# LED1_2.net
KiCad netlist of a schematic drawn in Altium Designer
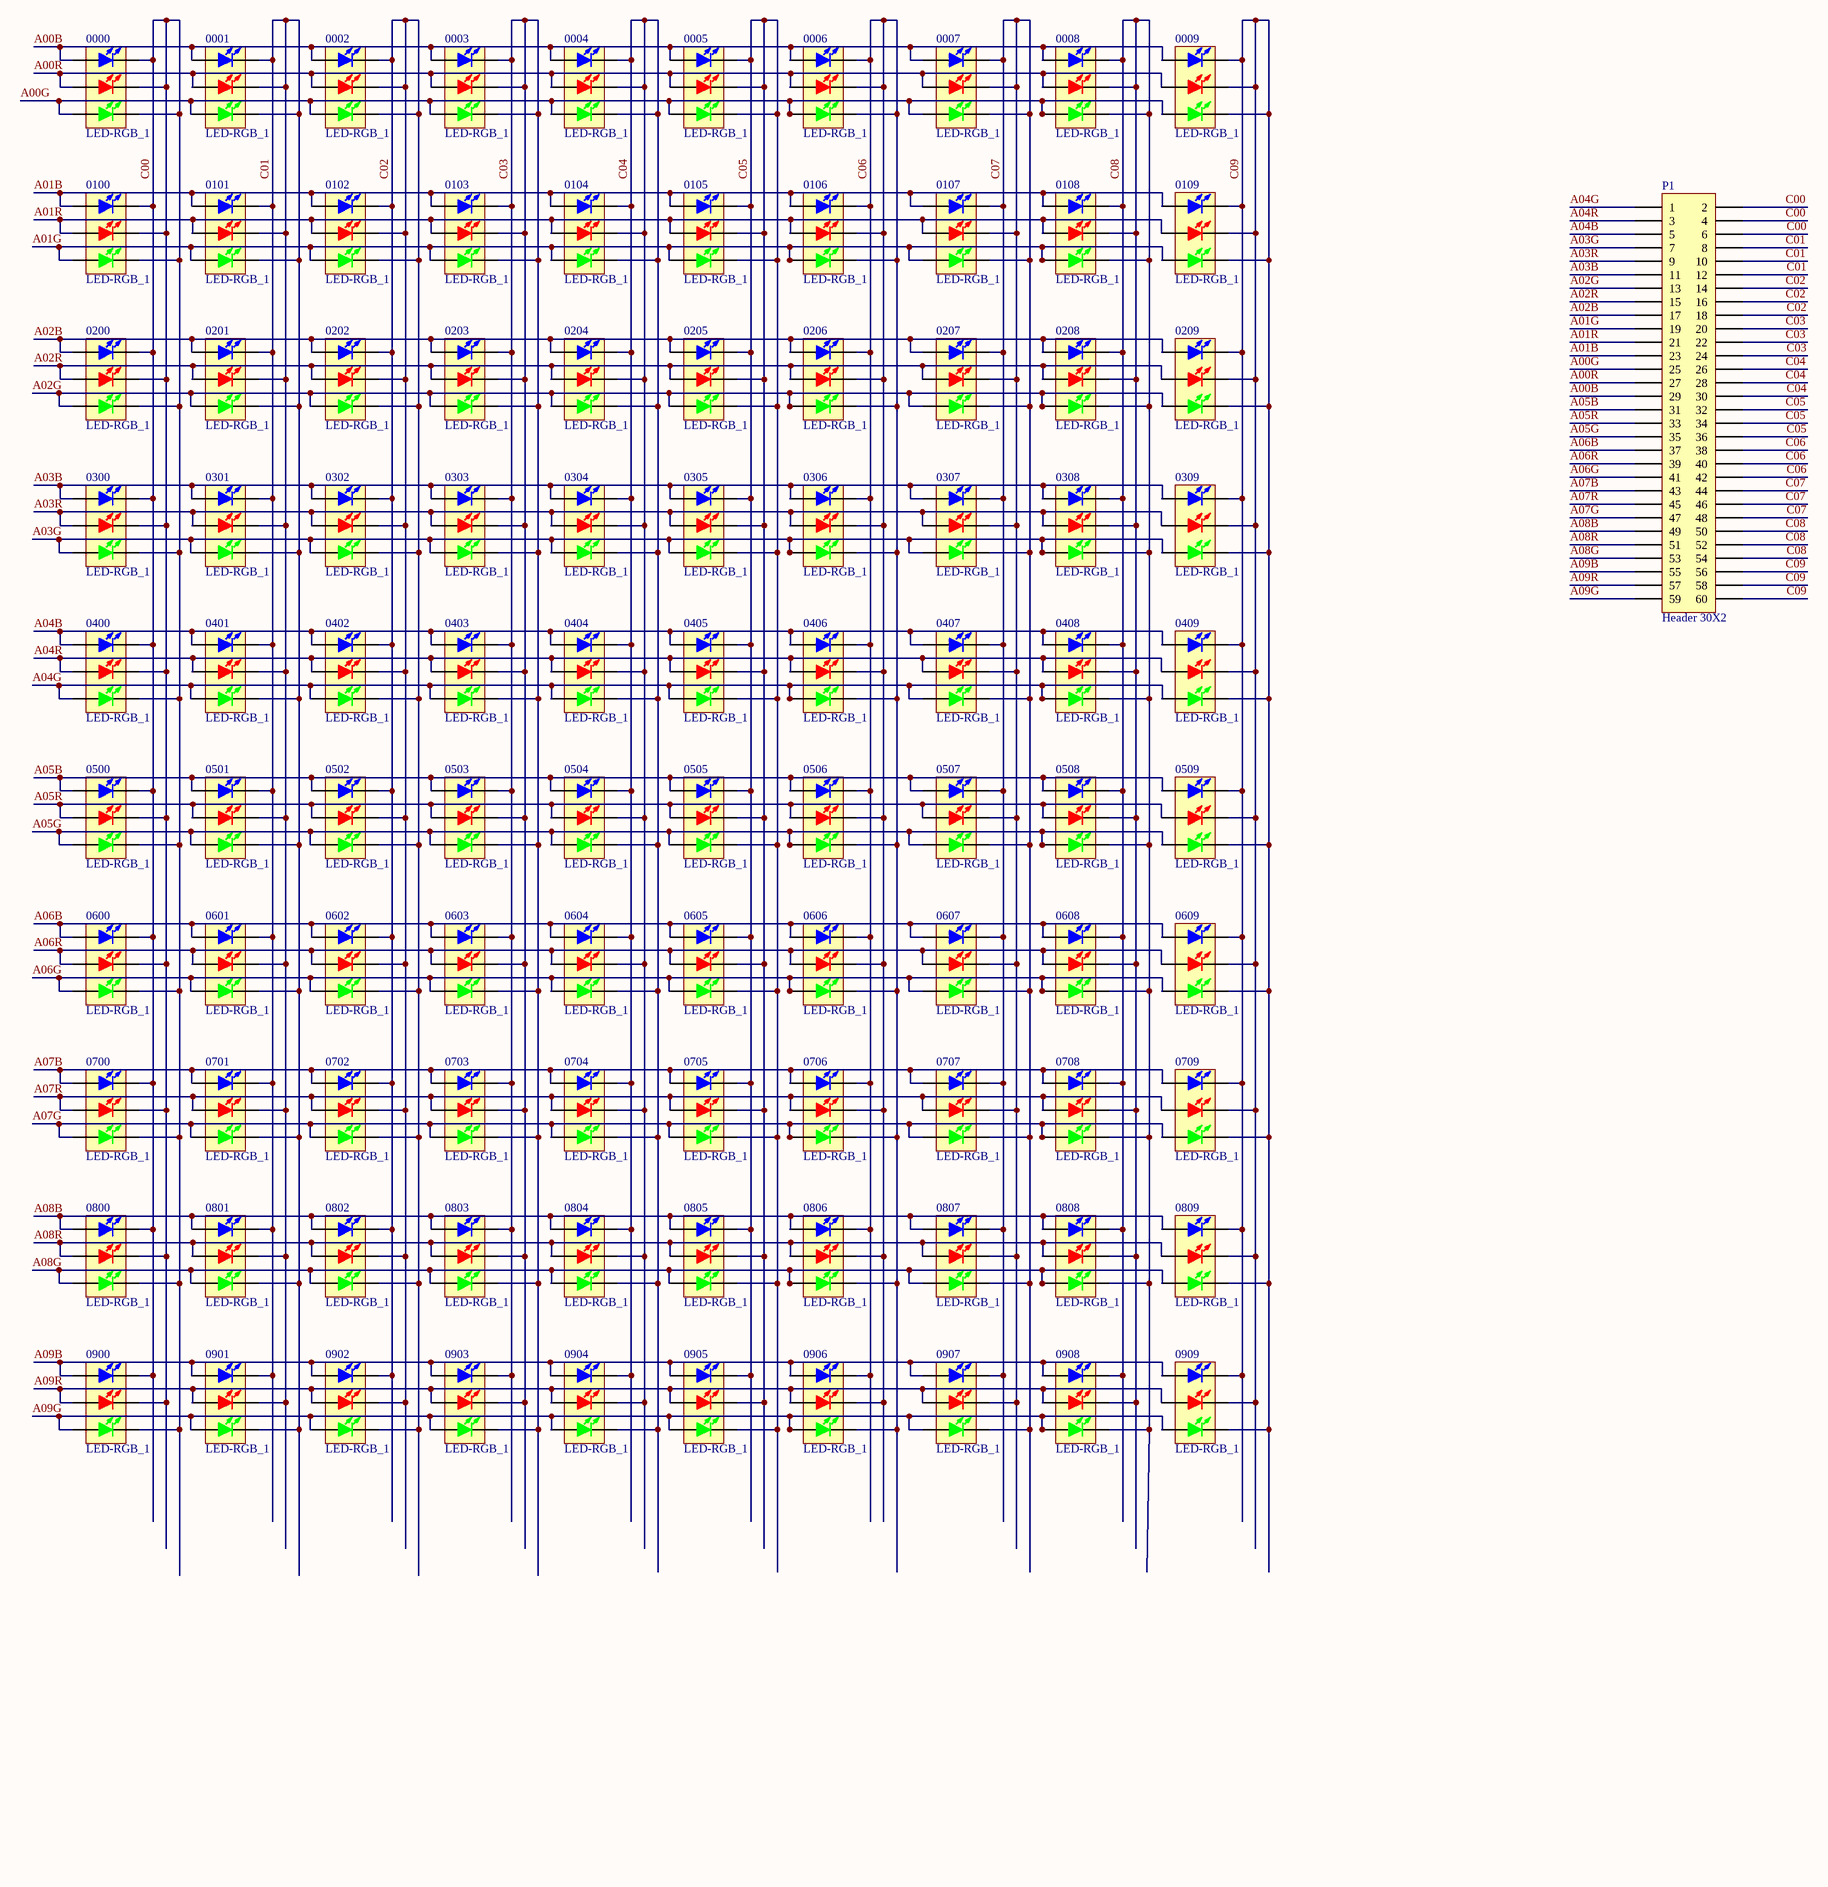
[diagram p0: LED1_2.SchDoc]

(export (version "E")
  (design (tool "Eeschema 10.0.6"))
  (components
    (comp (ref "0000")
      (value "LED-RGB_1")
      (footprint "LED 5050")
      (description "三基色LED,正负脚相对")
      (fields (field (name "版权归属") "源创客"))
      (libsource (lib "IL") (part "LED-RGB_1"))
    )
    (comp (ref "0001")
      (value "LED-RGB_1")
      (footprint "LED 5050")
      (description "三基色LED,正负脚相对")
      (fields (field (name "版权归属") "源创客"))
      (libsource (lib "IL") (part "LED-RGB_1"))
    )
    (comp (ref "0002")
      (value "LED-RGB_1")
      (footprint "LED 5050")
      (description "三基色LED,正负脚相对")
      (fields (field (name "版权归属") "源创客"))
      (libsource (lib "IL") (part "LED-RGB_1"))
    )
    (comp (ref "0003")
      (value "LED-RGB_1")
      (footprint "LED 5050")
      (description "三基色LED,正负脚相对")
      (fields (field (name "版权归属") "源创客"))
      (libsource (lib "IL") (part "LED-RGB_1"))
    )
    (comp (ref "0004")
      (value "LED-RGB_1")
      (footprint "LED 5050")
      (description "三基色LED,正负脚相对")
      (fields (field (name "版权归属") "源创客"))
      (libsource (lib "IL") (part "LED-RGB_1"))
    )
    (comp (ref "0005")
      (value "LED-RGB_1")
      (footprint "LED 5050")
      (description "三基色LED,正负脚相对")
      (fields (field (name "版权归属") "源创客"))
      (libsource (lib "IL") (part "LED-RGB_1"))
    )
    (comp (ref "0006")
      (value "LED-RGB_1")
      (footprint "LED 5050")
      (description "三基色LED,正负脚相对")
      (fields (field (name "版权归属") "源创客"))
      (libsource (lib "IL") (part "LED-RGB_1"))
    )
    (comp (ref "0007")
      (value "LED-RGB_1")
      (footprint "LED 5050")
      (description "三基色LED,正负脚相对")
      (fields (field (name "版权归属") "源创客"))
      (libsource (lib "IL") (part "LED-RGB_1"))
    )
    (comp (ref "0008")
      (value "LED-RGB_1")
      (footprint "LED 5050")
      (description "三基色LED,正负脚相对")
      (fields (field (name "版权归属") "源创客"))
      (libsource (lib "IL") (part "LED-RGB_1"))
    )
    (comp (ref "0009")
      (value "LED-RGB_1")
      (footprint "LED 5050")
      (description "三基色LED,正负脚相对")
      (fields (field (name "版权归属") "源创客"))
      (libsource (lib "IL") (part "LED-RGB_1"))
    )
    (comp (ref "0100")
      (value "LED-RGB_1")
      (footprint "LED 5050")
      (description "三基色LED,正负脚相对")
      (fields (field (name "版权归属") "源创客"))
      (libsource (lib "IL") (part "LED-RGB_1"))
    )
    (comp (ref "0101")
      (value "LED-RGB_1")
      (footprint "LED 5050")
      (description "三基色LED,正负脚相对")
      (fields (field (name "版权归属") "源创客"))
      (libsource (lib "IL") (part "LED-RGB_1"))
    )
    (comp (ref "0102")
      (value "LED-RGB_1")
      (footprint "LED 5050")
      (description "三基色LED,正负脚相对")
      (fields (field (name "版权归属") "源创客"))
      (libsource (lib "IL") (part "LED-RGB_1"))
    )
    (comp (ref "0103")
      (value "LED-RGB_1")
      (footprint "LED 5050")
      (description "三基色LED,正负脚相对")
      (fields (field (name "版权归属") "源创客"))
      (libsource (lib "IL") (part "LED-RGB_1"))
    )
    (comp (ref "0104")
      (value "LED-RGB_1")
      (footprint "LED 5050")
      (description "三基色LED,正负脚相对")
      (fields (field (name "版权归属") "源创客"))
      (libsource (lib "IL") (part "LED-RGB_1"))
    )
    (comp (ref "0105")
      (value "LED-RGB_1")
      (footprint "LED 5050")
      (description "三基色LED,正负脚相对")
      (fields (field (name "版权归属") "源创客"))
      (libsource (lib "IL") (part "LED-RGB_1"))
    )
    (comp (ref "0106")
      (value "LED-RGB_1")
      (footprint "LED 5050")
      (description "三基色LED,正负脚相对")
      (fields (field (name "版权归属") "源创客"))
      (libsource (lib "IL") (part "LED-RGB_1"))
    )
    (comp (ref "0107")
      (value "LED-RGB_1")
      (footprint "LED 5050")
      (description "三基色LED,正负脚相对")
      (fields (field (name "版权归属") "源创客"))
      (libsource (lib "IL") (part "LED-RGB_1"))
    )
    (comp (ref "0108")
      (value "LED-RGB_1")
      (footprint "LED 5050")
      (description "三基色LED,正负脚相对")
      (fields (field (name "版权归属") "源创客"))
      (libsource (lib "IL") (part "LED-RGB_1"))
    )
    (comp (ref "0109")
      (value "LED-RGB_1")
      (footprint "LED 5050")
      (description "三基色LED,正负脚相对")
      (fields (field (name "版权归属") "源创客"))
      (libsource (lib "IL") (part "LED-RGB_1"))
    )
    (comp (ref "0200")
      (value "LED-RGB_1")
      (footprint "LED 5050")
      (description "三基色LED,正负脚相对")
      (fields (field (name "版权归属") "源创客"))
      (libsource (lib "IL") (part "LED-RGB_1"))
    )
    (comp (ref "0201")
      (value "LED-RGB_1")
      (footprint "LED 5050")
      (description "三基色LED,正负脚相对")
      (fields (field (name "版权归属") "源创客"))
      (libsource (lib "IL") (part "LED-RGB_1"))
    )
    (comp (ref "0202")
      (value "LED-RGB_1")
      (footprint "LED 5050")
      (description "三基色LED,正负脚相对")
      (fields (field (name "版权归属") "源创客"))
      (libsource (lib "IL") (part "LED-RGB_1"))
    )
    (comp (ref "0203")
      (value "LED-RGB_1")
      (footprint "LED 5050")
      (description "三基色LED,正负脚相对")
      (fields (field (name "版权归属") "源创客"))
      (libsource (lib "IL") (part "LED-RGB_1"))
    )
    (comp (ref "0204")
      (value "LED-RGB_1")
      (footprint "LED 5050")
      (description "三基色LED,正负脚相对")
      (fields (field (name "版权归属") "源创客"))
      (libsource (lib "IL") (part "LED-RGB_1"))
    )
    (comp (ref "0205")
      (value "LED-RGB_1")
      (footprint "LED 5050")
      (description "三基色LED,正负脚相对")
      (fields (field (name "版权归属") "源创客"))
      (libsource (lib "IL") (part "LED-RGB_1"))
    )
    (comp (ref "0206")
      (value "LED-RGB_1")
      (footprint "LED 5050")
      (description "三基色LED,正负脚相对")
      (fields (field (name "版权归属") "源创客"))
      (libsource (lib "IL") (part "LED-RGB_1"))
    )
    (comp (ref "0207")
      (value "LED-RGB_1")
      (footprint "LED 5050")
      (description "三基色LED,正负脚相对")
      (fields (field (name "版权归属") "源创客"))
      (libsource (lib "IL") (part "LED-RGB_1"))
    )
    (comp (ref "0208")
      (value "LED-RGB_1")
      (footprint "LED 5050")
      (description "三基色LED,正负脚相对")
      (fields (field (name "版权归属") "源创客"))
      (libsource (lib "IL") (part "LED-RGB_1"))
    )
    (comp (ref "0209")
      (value "LED-RGB_1")
      (footprint "LED 5050")
      (description "三基色LED,正负脚相对")
      (fields (field (name "版权归属") "源创客"))
      (libsource (lib "IL") (part "LED-RGB_1"))
    )
    (comp (ref "0300")
      (value "LED-RGB_1")
      (footprint "LED 5050")
      (description "三基色LED,正负脚相对")
      (fields (field (name "版权归属") "源创客"))
      (libsource (lib "IL") (part "LED-RGB_1"))
    )
    (comp (ref "0301")
      (value "LED-RGB_1")
      (footprint "LED 5050")
      (description "三基色LED,正负脚相对")
      (fields (field (name "版权归属") "源创客"))
      (libsource (lib "IL") (part "LED-RGB_1"))
    )
    (comp (ref "0302")
      (value "LED-RGB_1")
      (footprint "LED 5050")
      (description "三基色LED,正负脚相对")
      (fields (field (name "版权归属") "源创客"))
      (libsource (lib "IL") (part "LED-RGB_1"))
    )
    (comp (ref "0303")
      (value "LED-RGB_1")
      (footprint "LED 5050")
      (description "三基色LED,正负脚相对")
      (fields (field (name "版权归属") "源创客"))
      (libsource (lib "IL") (part "LED-RGB_1"))
    )
    (comp (ref "0304")
      (value "LED-RGB_1")
      (footprint "LED 5050")
      (description "三基色LED,正负脚相对")
      (fields (field (name "版权归属") "源创客"))
      (libsource (lib "IL") (part "LED-RGB_1"))
    )
    (comp (ref "0305")
      (value "LED-RGB_1")
      (footprint "LED 5050")
      (description "三基色LED,正负脚相对")
      (fields (field (name "版权归属") "源创客"))
      (libsource (lib "IL") (part "LED-RGB_1"))
    )
    (comp (ref "0306")
      (value "LED-RGB_1")
      (footprint "LED 5050")
      (description "三基色LED,正负脚相对")
      (fields (field (name "版权归属") "源创客"))
      (libsource (lib "IL") (part "LED-RGB_1"))
    )
    (comp (ref "0307")
      (value "LED-RGB_1")
      (footprint "LED 5050")
      (description "三基色LED,正负脚相对")
      (fields (field (name "版权归属") "源创客"))
      (libsource (lib "IL") (part "LED-RGB_1"))
    )
    (comp (ref "0308")
      (value "LED-RGB_1")
      (footprint "LED 5050")
      (description "三基色LED,正负脚相对")
      (fields (field (name "版权归属") "源创客"))
      (libsource (lib "IL") (part "LED-RGB_1"))
    )
    (comp (ref "0309")
      (value "LED-RGB_1")
      (footprint "LED 5050")
      (description "三基色LED,正负脚相对")
      (fields (field (name "版权归属") "源创客"))
      (libsource (lib "IL") (part "LED-RGB_1"))
    )
    (comp (ref "0400")
      (value "LED-RGB_1")
      (footprint "LED 5050")
      (description "三基色LED,正负脚相对")
      (fields (field (name "版权归属") "源创客"))
      (libsource (lib "IL") (part "LED-RGB_1"))
    )
    (comp (ref "0401")
      (value "LED-RGB_1")
      (footprint "LED 5050")
      (description "三基色LED,正负脚相对")
      (fields (field (name "版权归属") "源创客"))
      (libsource (lib "IL") (part "LED-RGB_1"))
    )
    (comp (ref "0402")
      (value "LED-RGB_1")
      (footprint "LED 5050")
      (description "三基色LED,正负脚相对")
      (fields (field (name "版权归属") "源创客"))
      (libsource (lib "IL") (part "LED-RGB_1"))
    )
    (comp (ref "0403")
      (value "LED-RGB_1")
      (footprint "LED 5050")
      (description "三基色LED,正负脚相对")
      (fields (field (name "版权归属") "源创客"))
      (libsource (lib "IL") (part "LED-RGB_1"))
    )
    (comp (ref "0404")
      (value "LED-RGB_1")
      (footprint "LED 5050")
      (description "三基色LED,正负脚相对")
      (fields (field (name "版权归属") "源创客"))
      (libsource (lib "IL") (part "LED-RGB_1"))
    )
    (comp (ref "0405")
      (value "LED-RGB_1")
      (footprint "LED 5050")
      (description "三基色LED,正负脚相对")
      (fields (field (name "版权归属") "源创客"))
      (libsource (lib "IL") (part "LED-RGB_1"))
    )
    (comp (ref "0406")
      (value "LED-RGB_1")
      (footprint "LED 5050")
      (description "三基色LED,正负脚相对")
      (fields (field (name "版权归属") "源创客"))
      (libsource (lib "IL") (part "LED-RGB_1"))
    )
    (comp (ref "0407")
      (value "LED-RGB_1")
      (footprint "LED 5050")
      (description "三基色LED,正负脚相对")
      (fields (field (name "版权归属") "源创客"))
      (libsource (lib "IL") (part "LED-RGB_1"))
    )
    (comp (ref "0408")
      (value "LED-RGB_1")
      (footprint "LED 5050")
      (description "三基色LED,正负脚相对")
      (fields (field (name "版权归属") "源创客"))
      (libsource (lib "IL") (part "LED-RGB_1"))
    )
    (comp (ref "0409")
      (value "LED-RGB_1")
      (footprint "LED 5050")
      (description "三基色LED,正负脚相对")
      (fields (field (name "版权归属") "源创客"))
      (libsource (lib "IL") (part "LED-RGB_1"))
    )
    (comp (ref "0500")
      (value "LED-RGB_1")
      (footprint "LED 5050")
      (description "三基色LED,正负脚相对")
      (fields (field (name "版权归属") "源创客"))
      (libsource (lib "IL") (part "LED-RGB_1"))
    )
    (comp (ref "0501")
      (value "LED-RGB_1")
      (footprint "LED 5050")
      (description "三基色LED,正负脚相对")
      (fields (field (name "版权归属") "源创客"))
      (libsource (lib "IL") (part "LED-RGB_1"))
    )
    (comp (ref "0502")
      (value "LED-RGB_1")
      (footprint "LED 5050")
      (description "三基色LED,正负脚相对")
      (fields (field (name "版权归属") "源创客"))
      (libsource (lib "IL") (part "LED-RGB_1"))
    )
    (comp (ref "0503")
      (value "LED-RGB_1")
      (footprint "LED 5050")
      (description "三基色LED,正负脚相对")
      (fields (field (name "版权归属") "源创客"))
      (libsource (lib "IL") (part "LED-RGB_1"))
    )
    (comp (ref "0504")
      (value "LED-RGB_1")
      (footprint "LED 5050")
      (description "三基色LED,正负脚相对")
      (fields (field (name "版权归属") "源创客"))
      (libsource (lib "IL") (part "LED-RGB_1"))
    )
    (comp (ref "0505")
      (value "LED-RGB_1")
      (footprint "LED 5050")
      (description "三基色LED,正负脚相对")
      (fields (field (name "版权归属") "源创客"))
      (libsource (lib "IL") (part "LED-RGB_1"))
    )
    (comp (ref "0506")
      (value "LED-RGB_1")
      (footprint "LED 5050")
      (description "三基色LED,正负脚相对")
      (fields (field (name "版权归属") "源创客"))
      (libsource (lib "IL") (part "LED-RGB_1"))
    )
    (comp (ref "0507")
      (value "LED-RGB_1")
      (footprint "LED 5050")
      (description "三基色LED,正负脚相对")
      (fields (field (name "版权归属") "源创客"))
      (libsource (lib "IL") (part "LED-RGB_1"))
    )
    (comp (ref "0508")
      (value "LED-RGB_1")
      (footprint "LED 5050")
      (description "三基色LED,正负脚相对")
      (fields (field (name "版权归属") "源创客"))
      (libsource (lib "IL") (part "LED-RGB_1"))
    )
    (comp (ref "0509")
      (value "LED-RGB_1")
      (footprint "LED 5050")
      (description "三基色LED,正负脚相对")
      (fields (field (name "版权归属") "源创客"))
      (libsource (lib "IL") (part "LED-RGB_1"))
    )
    (comp (ref "0600")
      (value "LED-RGB_1")
      (footprint "LED 5050")
      (description "三基色LED,正负脚相对")
      (fields (field (name "版权归属") "源创客"))
      (libsource (lib "IL") (part "LED-RGB_1"))
    )
    (comp (ref "0601")
      (value "LED-RGB_1")
      (footprint "LED 5050")
      (description "三基色LED,正负脚相对")
      (fields (field (name "版权归属") "源创客"))
      (libsource (lib "IL") (part "LED-RGB_1"))
    )
    (comp (ref "0602")
      (value "LED-RGB_1")
      (footprint "LED 5050")
      (description "三基色LED,正负脚相对")
      (fields (field (name "版权归属") "源创客"))
      (libsource (lib "IL") (part "LED-RGB_1"))
    )
    (comp (ref "0603")
      (value "LED-RGB_1")
      (footprint "LED 5050")
      (description "三基色LED,正负脚相对")
      (fields (field (name "版权归属") "源创客"))
      (libsource (lib "IL") (part "LED-RGB_1"))
    )
    (comp (ref "0604")
      (value "LED-RGB_1")
      (footprint "LED 5050")
      (description "三基色LED,正负脚相对")
      (fields (field (name "版权归属") "源创客"))
      (libsource (lib "IL") (part "LED-RGB_1"))
    )
    (comp (ref "0605")
      (value "LED-RGB_1")
      (footprint "LED 5050")
      (description "三基色LED,正负脚相对")
      (fields (field (name "版权归属") "源创客"))
      (libsource (lib "IL") (part "LED-RGB_1"))
    )
    (comp (ref "0606")
      (value "LED-RGB_1")
      (footprint "LED 5050")
      (description "三基色LED,正负脚相对")
      (fields (field (name "版权归属") "源创客"))
      (libsource (lib "IL") (part "LED-RGB_1"))
    )
    (comp (ref "0607")
      (value "LED-RGB_1")
      (footprint "LED 5050")
      (description "三基色LED,正负脚相对")
      (fields (field (name "版权归属") "源创客"))
      (libsource (lib "IL") (part "LED-RGB_1"))
    )
    (comp (ref "0608")
      (value "LED-RGB_1")
      (footprint "LED 5050")
      (description "三基色LED,正负脚相对")
      (fields (field (name "版权归属") "源创客"))
      (libsource (lib "IL") (part "LED-RGB_1"))
    )
    (comp (ref "0609")
      (value "LED-RGB_1")
      (footprint "LED 5050")
      (description "三基色LED,正负脚相对")
      (fields (field (name "版权归属") "源创客"))
      (libsource (lib "IL") (part "LED-RGB_1"))
    )
    (comp (ref "0700")
      (value "LED-RGB_1")
      (footprint "LED 5050")
      (description "三基色LED,正负脚相对")
      (fields (field (name "版权归属") "源创客"))
      (libsource (lib "IL") (part "LED-RGB_1"))
    )
    (comp (ref "0701")
      (value "LED-RGB_1")
      (footprint "LED 5050")
      (description "三基色LED,正负脚相对")
      (fields (field (name "版权归属") "源创客"))
      (libsource (lib "IL") (part "LED-RGB_1"))
    )
    (comp (ref "0702")
      (value "LED-RGB_1")
      (footprint "LED 5050")
      (description "三基色LED,正负脚相对")
      (fields (field (name "版权归属") "源创客"))
      (libsource (lib "IL") (part "LED-RGB_1"))
    )
    (comp (ref "0703")
      (value "LED-RGB_1")
      (footprint "LED 5050")
      (description "三基色LED,正负脚相对")
      (fields (field (name "版权归属") "源创客"))
      (libsource (lib "IL") (part "LED-RGB_1"))
    )
    (comp (ref "0704")
      (value "LED-RGB_1")
      (footprint "LED 5050")
      (description "三基色LED,正负脚相对")
      (fields (field (name "版权归属") "源创客"))
      (libsource (lib "IL") (part "LED-RGB_1"))
    )
    (comp (ref "0705")
      (value "LED-RGB_1")
      (footprint "LED 5050")
      (description "三基色LED,正负脚相对")
      (fields (field (name "版权归属") "源创客"))
      (libsource (lib "IL") (part "LED-RGB_1"))
    )
    (comp (ref "0706")
      (value "LED-RGB_1")
      (footprint "LED 5050")
      (description "三基色LED,正负脚相对")
      (fields (field (name "版权归属") "源创客"))
      (libsource (lib "IL") (part "LED-RGB_1"))
    )
    (comp (ref "0707")
      (value "LED-RGB_1")
      (footprint "LED 5050")
      (description "三基色LED,正负脚相对")
      (fields (field (name "版权归属") "源创客"))
      (libsource (lib "IL") (part "LED-RGB_1"))
    )
    (comp (ref "0708")
      (value "LED-RGB_1")
      (footprint "LED 5050")
      (description "三基色LED,正负脚相对")
      (fields (field (name "版权归属") "源创客"))
      (libsource (lib "IL") (part "LED-RGB_1"))
    )
    (comp (ref "0709")
      (value "LED-RGB_1")
      (footprint "LED 5050")
      (description "三基色LED,正负脚相对")
      (fields (field (name "版权归属") "源创客"))
      (libsource (lib "IL") (part "LED-RGB_1"))
    )
    (comp (ref "0800")
      (value "LED-RGB_1")
      (footprint "LED 5050")
      (description "三基色LED,正负脚相对")
      (fields (field (name "版权归属") "源创客"))
      (libsource (lib "IL") (part "LED-RGB_1"))
    )
    (comp (ref "0801")
      (value "LED-RGB_1")
      (footprint "LED 5050")
      (description "三基色LED,正负脚相对")
      (fields (field (name "版权归属") "源创客"))
      (libsource (lib "IL") (part "LED-RGB_1"))
    )
    (comp (ref "0802")
      (value "LED-RGB_1")
      (footprint "LED 5050")
      (description "三基色LED,正负脚相对")
      (fields (field (name "版权归属") "源创客"))
      (libsource (lib "IL") (part "LED-RGB_1"))
    )
    (comp (ref "0803")
      (value "LED-RGB_1")
      (footprint "LED 5050")
      (description "三基色LED,正负脚相对")
      (fields (field (name "版权归属") "源创客"))
      (libsource (lib "IL") (part "LED-RGB_1"))
    )
    (comp (ref "0804")
      (value "LED-RGB_1")
      (footprint "LED 5050")
      (description "三基色LED,正负脚相对")
      (fields (field (name "版权归属") "源创客"))
      (libsource (lib "IL") (part "LED-RGB_1"))
    )
    (comp (ref "0805")
      (value "LED-RGB_1")
      (footprint "LED 5050")
      (description "三基色LED,正负脚相对")
      (fields (field (name "版权归属") "源创客"))
      (libsource (lib "IL") (part "LED-RGB_1"))
    )
    (comp (ref "0806")
      (value "LED-RGB_1")
      (footprint "LED 5050")
      (description "三基色LED,正负脚相对")
      (fields (field (name "版权归属") "源创客"))
      (libsource (lib "IL") (part "LED-RGB_1"))
    )
    (comp (ref "0807")
      (value "LED-RGB_1")
      (footprint "LED 5050")
      (description "三基色LED,正负脚相对")
      (fields (field (name "版权归属") "源创客"))
      (libsource (lib "IL") (part "LED-RGB_1"))
    )
    (comp (ref "0808")
      (value "LED-RGB_1")
      (footprint "LED 5050")
      (description "三基色LED,正负脚相对")
      (fields (field (name "版权归属") "源创客"))
      (libsource (lib "IL") (part "LED-RGB_1"))
    )
    (comp (ref "0809")
      (value "LED-RGB_1")
      (footprint "LED 5050")
      (description "三基色LED,正负脚相对")
      (fields (field (name "版权归属") "源创客"))
      (libsource (lib "IL") (part "LED-RGB_1"))
    )
    (comp (ref "0900")
      (value "LED-RGB_1")
      (footprint "LED 5050")
      (description "三基色LED,正负脚相对")
      (fields (field (name "版权归属") "源创客"))
      (libsource (lib "IL") (part "LED-RGB_1"))
    )
    (comp (ref "0901")
      (value "LED-RGB_1")
      (footprint "LED 5050")
      (description "三基色LED,正负脚相对")
      (fields (field (name "版权归属") "源创客"))
      (libsource (lib "IL") (part "LED-RGB_1"))
    )
    (comp (ref "0902")
      (value "LED-RGB_1")
      (footprint "LED 5050")
      (description "三基色LED,正负脚相对")
      (fields (field (name "版权归属") "源创客"))
      (libsource (lib "IL") (part "LED-RGB_1"))
    )
    (comp (ref "0903")
      (value "LED-RGB_1")
      (footprint "LED 5050")
      (description "三基色LED,正负脚相对")
      (fields (field (name "版权归属") "源创客"))
      (libsource (lib "IL") (part "LED-RGB_1"))
    )
    (comp (ref "0904")
      (value "LED-RGB_1")
      (footprint "LED 5050")
      (description "三基色LED,正负脚相对")
      (fields (field (name "版权归属") "源创客"))
      (libsource (lib "IL") (part "LED-RGB_1"))
    )
    (comp (ref "0905")
      (value "LED-RGB_1")
      (footprint "LED 5050")
      (description "三基色LED,正负脚相对")
      (fields (field (name "版权归属") "源创客"))
      (libsource (lib "IL") (part "LED-RGB_1"))
    )
    (comp (ref "0906")
      (value "LED-RGB_1")
      (footprint "LED 5050")
      (description "三基色LED,正负脚相对")
      (fields (field (name "版权归属") "源创客"))
      (libsource (lib "IL") (part "LED-RGB_1"))
    )
    (comp (ref "0907")
      (value "LED-RGB_1")
      (footprint "LED 5050")
      (description "三基色LED,正负脚相对")
      (fields (field (name "版权归属") "源创客"))
      (libsource (lib "IL") (part "LED-RGB_1"))
    )
    (comp (ref "0908")
      (value "LED-RGB_1")
      (footprint "LED 5050")
      (description "三基色LED,正负脚相对")
      (fields (field (name "版权归属") "源创客"))
      (libsource (lib "IL") (part "LED-RGB_1"))
    )
    (comp (ref "0909")
      (value "LED-RGB_1")
      (footprint "LED 5050")
      (description "三基色LED,正负脚相对")
      (fields (field (name "版权归属") "源创客"))
      (libsource (lib "IL") (part "LED-RGB_1"))
    )
    (comp (ref "P1")
      (value "Header 30X2")
      (footprint "HDR2X30")
      (description "Header, 30-Pin, Dual row")
      (fields (field (name "PUBLISHER") "Altium Limited"))
      (libsource (lib "Miscellaneous Connectors") (part "Header 30X2"))
    )
  )
  (nets
    (net (code "1") (name "/A00B") (class "Default")
      (node (ref "0000") (pin "1") (pinfunction "BULE_A_1") (pintype "passive"))
      (node (ref "0001") (pin "1") (pinfunction "BULE_A_1") (pintype "passive"))
      (node (ref "0002") (pin "1") (pinfunction "BULE_A_1") (pintype "passive"))
      (node (ref "0003") (pin "1") (pinfunction "BULE_A_1") (pintype "passive"))
      (node (ref "0004") (pin "1") (pinfunction "BULE_A_1") (pintype "passive"))
      (node (ref "0005") (pin "1") (pinfunction "BULE_A_1") (pintype "passive"))
      (node (ref "0006") (pin "1") (pinfunction "BULE_A_1") (pintype "passive"))
      (node (ref "0007") (pin "1") (pinfunction "BULE_A_1") (pintype "passive"))
      (node (ref "0008") (pin "1") (pinfunction "BULE_A_1") (pintype "passive"))
      (node (ref "0009") (pin "1") (pinfunction "BULE_A_1") (pintype "passive"))
      (node (ref "P1") (pin "29") (pinfunction "29_29") (pintype "passive"))
    )
    (net (code "2") (name "/A00G") (class "Default")
      (node (ref "0000") (pin "5") (pinfunction "GREEN_A_5") (pintype "passive"))
      (node (ref "0001") (pin "5") (pinfunction "GREEN_A_5") (pintype "passive"))
      (node (ref "0002") (pin "5") (pinfunction "GREEN_A_5") (pintype "passive"))
      (node (ref "0003") (pin "5") (pinfunction "GREEN_A_5") (pintype "passive"))
      (node (ref "0004") (pin "5") (pinfunction "GREEN_A_5") (pintype "passive"))
      (node (ref "0005") (pin "5") (pinfunction "GREEN_A_5") (pintype "passive"))
      (node (ref "0006") (pin "5") (pinfunction "GREEN_A_5") (pintype "passive"))
      (node (ref "0007") (pin "5") (pinfunction "GREEN_A_5") (pintype "passive"))
      (node (ref "0008") (pin "5") (pinfunction "GREEN_A_5") (pintype "passive"))
      (node (ref "0009") (pin "5") (pinfunction "GREEN_A_5") (pintype "passive"))
      (node (ref "P1") (pin "25") (pinfunction "25_25") (pintype "passive"))
    )
    (net (code "3") (name "/A00R") (class "Default")
      (node (ref "0000") (pin "3") (pinfunction "RED_A_3") (pintype "passive"))
      (node (ref "0001") (pin "3") (pinfunction "RED_A_3") (pintype "passive"))
      (node (ref "0002") (pin "3") (pinfunction "RED_A_3") (pintype "passive"))
      (node (ref "0003") (pin "3") (pinfunction "RED_A_3") (pintype "passive"))
      (node (ref "0004") (pin "3") (pinfunction "RED_A_3") (pintype "passive"))
      (node (ref "0005") (pin "3") (pinfunction "RED_A_3") (pintype "passive"))
      (node (ref "0006") (pin "3") (pinfunction "RED_A_3") (pintype "passive"))
      (node (ref "0007") (pin "3") (pinfunction "RED_A_3") (pintype "passive"))
      (node (ref "0008") (pin "3") (pinfunction "RED_A_3") (pintype "passive"))
      (node (ref "0009") (pin "3") (pinfunction "RED_A_3") (pintype "passive"))
      (node (ref "P1") (pin "27") (pinfunction "27_27") (pintype "passive"))
    )
    (net (code "4") (name "/A01B") (class "Default")
      (node (ref "0100") (pin "1") (pinfunction "BULE_A_1") (pintype "passive"))
      (node (ref "0101") (pin "1") (pinfunction "BULE_A_1") (pintype "passive"))
      (node (ref "0102") (pin "1") (pinfunction "BULE_A_1") (pintype "passive"))
      (node (ref "0103") (pin "1") (pinfunction "BULE_A_1") (pintype "passive"))
      (node (ref "0104") (pin "1") (pinfunction "BULE_A_1") (pintype "passive"))
      (node (ref "0105") (pin "1") (pinfunction "BULE_A_1") (pintype "passive"))
      (node (ref "0106") (pin "1") (pinfunction "BULE_A_1") (pintype "passive"))
      (node (ref "0107") (pin "1") (pinfunction "BULE_A_1") (pintype "passive"))
      (node (ref "0108") (pin "1") (pinfunction "BULE_A_1") (pintype "passive"))
      (node (ref "0109") (pin "1") (pinfunction "BULE_A_1") (pintype "passive"))
      (node (ref "P1") (pin "23") (pinfunction "23_23") (pintype "passive"))
    )
    (net (code "5") (name "/A01G") (class "Default")
      (node (ref "0100") (pin "5") (pinfunction "GREEN_A_5") (pintype "passive"))
      (node (ref "0101") (pin "5") (pinfunction "GREEN_A_5") (pintype "passive"))
      (node (ref "0102") (pin "5") (pinfunction "GREEN_A_5") (pintype "passive"))
      (node (ref "0103") (pin "5") (pinfunction "GREEN_A_5") (pintype "passive"))
      (node (ref "0104") (pin "5") (pinfunction "GREEN_A_5") (pintype "passive"))
      (node (ref "0105") (pin "5") (pinfunction "GREEN_A_5") (pintype "passive"))
      (node (ref "0106") (pin "5") (pinfunction "GREEN_A_5") (pintype "passive"))
      (node (ref "0107") (pin "5") (pinfunction "GREEN_A_5") (pintype "passive"))
      (node (ref "0108") (pin "5") (pinfunction "GREEN_A_5") (pintype "passive"))
      (node (ref "0109") (pin "5") (pinfunction "GREEN_A_5") (pintype "passive"))
      (node (ref "P1") (pin "19") (pinfunction "19_19") (pintype "passive"))
    )
    (net (code "6") (name "/A01R") (class "Default")
      (node (ref "0100") (pin "3") (pinfunction "RED_A_3") (pintype "passive"))
      (node (ref "0101") (pin "3") (pinfunction "RED_A_3") (pintype "passive"))
      (node (ref "0102") (pin "3") (pinfunction "RED_A_3") (pintype "passive"))
      (node (ref "0103") (pin "3") (pinfunction "RED_A_3") (pintype "passive"))
      (node (ref "0104") (pin "3") (pinfunction "RED_A_3") (pintype "passive"))
      (node (ref "0105") (pin "3") (pinfunction "RED_A_3") (pintype "passive"))
      (node (ref "0106") (pin "3") (pinfunction "RED_A_3") (pintype "passive"))
      (node (ref "0107") (pin "3") (pinfunction "RED_A_3") (pintype "passive"))
      (node (ref "0108") (pin "3") (pinfunction "RED_A_3") (pintype "passive"))
      (node (ref "0109") (pin "3") (pinfunction "RED_A_3") (pintype "passive"))
      (node (ref "P1") (pin "21") (pinfunction "21_21") (pintype "passive"))
    )
    (net (code "7") (name "/A02B") (class "Default")
      (node (ref "0200") (pin "1") (pinfunction "BULE_A_1") (pintype "passive"))
      (node (ref "0201") (pin "1") (pinfunction "BULE_A_1") (pintype "passive"))
      (node (ref "0202") (pin "1") (pinfunction "BULE_A_1") (pintype "passive"))
      (node (ref "0203") (pin "1") (pinfunction "BULE_A_1") (pintype "passive"))
      (node (ref "0204") (pin "1") (pinfunction "BULE_A_1") (pintype "passive"))
      (node (ref "0205") (pin "1") (pinfunction "BULE_A_1") (pintype "passive"))
      (node (ref "0206") (pin "1") (pinfunction "BULE_A_1") (pintype "passive"))
      (node (ref "0207") (pin "1") (pinfunction "BULE_A_1") (pintype "passive"))
      (node (ref "0208") (pin "1") (pinfunction "BULE_A_1") (pintype "passive"))
      (node (ref "0209") (pin "1") (pinfunction "BULE_A_1") (pintype "passive"))
      (node (ref "P1") (pin "17") (pinfunction "17_17") (pintype "passive"))
    )
    (net (code "8") (name "/A02G") (class "Default")
      (node (ref "0200") (pin "5") (pinfunction "GREEN_A_5") (pintype "passive"))
      (node (ref "0201") (pin "5") (pinfunction "GREEN_A_5") (pintype "passive"))
      (node (ref "0202") (pin "5") (pinfunction "GREEN_A_5") (pintype "passive"))
      (node (ref "0203") (pin "5") (pinfunction "GREEN_A_5") (pintype "passive"))
      (node (ref "0204") (pin "5") (pinfunction "GREEN_A_5") (pintype "passive"))
      (node (ref "0205") (pin "5") (pinfunction "GREEN_A_5") (pintype "passive"))
      (node (ref "0206") (pin "5") (pinfunction "GREEN_A_5") (pintype "passive"))
      (node (ref "0207") (pin "5") (pinfunction "GREEN_A_5") (pintype "passive"))
      (node (ref "0208") (pin "5") (pinfunction "GREEN_A_5") (pintype "passive"))
      (node (ref "0209") (pin "5") (pinfunction "GREEN_A_5") (pintype "passive"))
      (node (ref "P1") (pin "13") (pinfunction "13_13") (pintype "passive"))
    )
    (net (code "9") (name "/A02R") (class "Default")
      (node (ref "0200") (pin "3") (pinfunction "RED_A_3") (pintype "passive"))
      (node (ref "0201") (pin "3") (pinfunction "RED_A_3") (pintype "passive"))
      (node (ref "0202") (pin "3") (pinfunction "RED_A_3") (pintype "passive"))
      (node (ref "0203") (pin "3") (pinfunction "RED_A_3") (pintype "passive"))
      (node (ref "0204") (pin "3") (pinfunction "RED_A_3") (pintype "passive"))
      (node (ref "0205") (pin "3") (pinfunction "RED_A_3") (pintype "passive"))
      (node (ref "0206") (pin "3") (pinfunction "RED_A_3") (pintype "passive"))
      (node (ref "0207") (pin "3") (pinfunction "RED_A_3") (pintype "passive"))
      (node (ref "0208") (pin "3") (pinfunction "RED_A_3") (pintype "passive"))
      (node (ref "0209") (pin "3") (pinfunction "RED_A_3") (pintype "passive"))
      (node (ref "P1") (pin "15") (pinfunction "15_15") (pintype "passive"))
    )
    (net (code "10") (name "/A03B") (class "Default")
      (node (ref "0300") (pin "1") (pinfunction "BULE_A_1") (pintype "passive"))
      (node (ref "0301") (pin "1") (pinfunction "BULE_A_1") (pintype "passive"))
      (node (ref "0302") (pin "1") (pinfunction "BULE_A_1") (pintype "passive"))
      (node (ref "0303") (pin "1") (pinfunction "BULE_A_1") (pintype "passive"))
      (node (ref "0304") (pin "1") (pinfunction "BULE_A_1") (pintype "passive"))
      (node (ref "0305") (pin "1") (pinfunction "BULE_A_1") (pintype "passive"))
      (node (ref "0306") (pin "1") (pinfunction "BULE_A_1") (pintype "passive"))
      (node (ref "0307") (pin "1") (pinfunction "BULE_A_1") (pintype "passive"))
      (node (ref "0308") (pin "1") (pinfunction "BULE_A_1") (pintype "passive"))
      (node (ref "0309") (pin "1") (pinfunction "BULE_A_1") (pintype "passive"))
      (node (ref "P1") (pin "11") (pinfunction "11_11") (pintype "passive"))
    )
    (net (code "11") (name "/A03G") (class "Default")
      (node (ref "0300") (pin "5") (pinfunction "GREEN_A_5") (pintype "passive"))
      (node (ref "0301") (pin "5") (pinfunction "GREEN_A_5") (pintype "passive"))
      (node (ref "0302") (pin "5") (pinfunction "GREEN_A_5") (pintype "passive"))
      (node (ref "0303") (pin "5") (pinfunction "GREEN_A_5") (pintype "passive"))
      (node (ref "0304") (pin "5") (pinfunction "GREEN_A_5") (pintype "passive"))
      (node (ref "0305") (pin "5") (pinfunction "GREEN_A_5") (pintype "passive"))
      (node (ref "0306") (pin "5") (pinfunction "GREEN_A_5") (pintype "passive"))
      (node (ref "0307") (pin "5") (pinfunction "GREEN_A_5") (pintype "passive"))
      (node (ref "0308") (pin "5") (pinfunction "GREEN_A_5") (pintype "passive"))
      (node (ref "0309") (pin "5") (pinfunction "GREEN_A_5") (pintype "passive"))
      (node (ref "P1") (pin "7") (pinfunction "7_7") (pintype "passive"))
    )
    (net (code "12") (name "/A03R") (class "Default")
      (node (ref "0300") (pin "3") (pinfunction "RED_A_3") (pintype "passive"))
      (node (ref "0301") (pin "3") (pinfunction "RED_A_3") (pintype "passive"))
      (node (ref "0302") (pin "3") (pinfunction "RED_A_3") (pintype "passive"))
      (node (ref "0303") (pin "3") (pinfunction "RED_A_3") (pintype "passive"))
      (node (ref "0304") (pin "3") (pinfunction "RED_A_3") (pintype "passive"))
      (node (ref "0305") (pin "3") (pinfunction "RED_A_3") (pintype "passive"))
      (node (ref "0306") (pin "3") (pinfunction "RED_A_3") (pintype "passive"))
      (node (ref "0307") (pin "3") (pinfunction "RED_A_3") (pintype "passive"))
      (node (ref "0308") (pin "3") (pinfunction "RED_A_3") (pintype "passive"))
      (node (ref "0309") (pin "3") (pinfunction "RED_A_3") (pintype "passive"))
      (node (ref "P1") (pin "9") (pinfunction "9_9") (pintype "passive"))
    )
    (net (code "13") (name "/A04B") (class "Default")
      (node (ref "0400") (pin "1") (pinfunction "BULE_A_1") (pintype "passive"))
      (node (ref "0401") (pin "1") (pinfunction "BULE_A_1") (pintype "passive"))
      (node (ref "0402") (pin "1") (pinfunction "BULE_A_1") (pintype "passive"))
      (node (ref "0403") (pin "1") (pinfunction "BULE_A_1") (pintype "passive"))
      (node (ref "0404") (pin "1") (pinfunction "BULE_A_1") (pintype "passive"))
      (node (ref "0405") (pin "1") (pinfunction "BULE_A_1") (pintype "passive"))
      (node (ref "0406") (pin "1") (pinfunction "BULE_A_1") (pintype "passive"))
      (node (ref "0407") (pin "1") (pinfunction "BULE_A_1") (pintype "passive"))
      (node (ref "0408") (pin "1") (pinfunction "BULE_A_1") (pintype "passive"))
      (node (ref "0409") (pin "1") (pinfunction "BULE_A_1") (pintype "passive"))
      (node (ref "P1") (pin "5") (pinfunction "5_5") (pintype "passive"))
    )
    (net (code "14") (name "/A04G") (class "Default")
      (node (ref "0400") (pin "5") (pinfunction "GREEN_A_5") (pintype "passive"))
      (node (ref "0401") (pin "5") (pinfunction "GREEN_A_5") (pintype "passive"))
      (node (ref "0402") (pin "5") (pinfunction "GREEN_A_5") (pintype "passive"))
      (node (ref "0403") (pin "5") (pinfunction "GREEN_A_5") (pintype "passive"))
      (node (ref "0404") (pin "5") (pinfunction "GREEN_A_5") (pintype "passive"))
      (node (ref "0405") (pin "5") (pinfunction "GREEN_A_5") (pintype "passive"))
      (node (ref "0406") (pin "5") (pinfunction "GREEN_A_5") (pintype "passive"))
      (node (ref "0407") (pin "5") (pinfunction "GREEN_A_5") (pintype "passive"))
      (node (ref "0408") (pin "5") (pinfunction "GREEN_A_5") (pintype "passive"))
      (node (ref "0409") (pin "5") (pinfunction "GREEN_A_5") (pintype "passive"))
      (node (ref "P1") (pin "1") (pinfunction "1_1") (pintype "passive"))
    )
    (net (code "15") (name "/A04R") (class "Default")
      (node (ref "0400") (pin "3") (pinfunction "RED_A_3") (pintype "passive"))
      (node (ref "0401") (pin "3") (pinfunction "RED_A_3") (pintype "passive"))
      (node (ref "0402") (pin "3") (pinfunction "RED_A_3") (pintype "passive"))
      (node (ref "0403") (pin "3") (pinfunction "RED_A_3") (pintype "passive"))
      (node (ref "0404") (pin "3") (pinfunction "RED_A_3") (pintype "passive"))
      (node (ref "0405") (pin "3") (pinfunction "RED_A_3") (pintype "passive"))
      (node (ref "0406") (pin "3") (pinfunction "RED_A_3") (pintype "passive"))
      (node (ref "0407") (pin "3") (pinfunction "RED_A_3") (pintype "passive"))
      (node (ref "0408") (pin "3") (pinfunction "RED_A_3") (pintype "passive"))
      (node (ref "0409") (pin "3") (pinfunction "RED_A_3") (pintype "passive"))
      (node (ref "P1") (pin "3") (pinfunction "3_3") (pintype "passive"))
    )
    (net (code "16") (name "/A05B") (class "Default")
      (node (ref "0500") (pin "1") (pinfunction "BULE_A_1") (pintype "passive"))
      (node (ref "0501") (pin "1") (pinfunction "BULE_A_1") (pintype "passive"))
      (node (ref "0502") (pin "1") (pinfunction "BULE_A_1") (pintype "passive"))
      (node (ref "0503") (pin "1") (pinfunction "BULE_A_1") (pintype "passive"))
      (node (ref "0504") (pin "1") (pinfunction "BULE_A_1") (pintype "passive"))
      (node (ref "0505") (pin "1") (pinfunction "BULE_A_1") (pintype "passive"))
      (node (ref "0506") (pin "1") (pinfunction "BULE_A_1") (pintype "passive"))
      (node (ref "0507") (pin "1") (pinfunction "BULE_A_1") (pintype "passive"))
      (node (ref "0508") (pin "1") (pinfunction "BULE_A_1") (pintype "passive"))
      (node (ref "0509") (pin "1") (pinfunction "BULE_A_1") (pintype "passive"))
      (node (ref "P1") (pin "31") (pinfunction "31_31") (pintype "passive"))
    )
    (net (code "17") (name "/A05G") (class "Default")
      (node (ref "0500") (pin "5") (pinfunction "GREEN_A_5") (pintype "passive"))
      (node (ref "0501") (pin "5") (pinfunction "GREEN_A_5") (pintype "passive"))
      (node (ref "0502") (pin "5") (pinfunction "GREEN_A_5") (pintype "passive"))
      (node (ref "0503") (pin "5") (pinfunction "GREEN_A_5") (pintype "passive"))
      (node (ref "0504") (pin "5") (pinfunction "GREEN_A_5") (pintype "passive"))
      (node (ref "0505") (pin "5") (pinfunction "GREEN_A_5") (pintype "passive"))
      (node (ref "0506") (pin "5") (pinfunction "GREEN_A_5") (pintype "passive"))
      (node (ref "0507") (pin "5") (pinfunction "GREEN_A_5") (pintype "passive"))
      (node (ref "0508") (pin "5") (pinfunction "GREEN_A_5") (pintype "passive"))
      (node (ref "0509") (pin "5") (pinfunction "GREEN_A_5") (pintype "passive"))
      (node (ref "P1") (pin "35") (pinfunction "35_35") (pintype "passive"))
    )
    (net (code "18") (name "/A05R") (class "Default")
      (node (ref "0500") (pin "3") (pinfunction "RED_A_3") (pintype "passive"))
      (node (ref "0501") (pin "3") (pinfunction "RED_A_3") (pintype "passive"))
      (node (ref "0502") (pin "3") (pinfunction "RED_A_3") (pintype "passive"))
      (node (ref "0503") (pin "3") (pinfunction "RED_A_3") (pintype "passive"))
      (node (ref "0504") (pin "3") (pinfunction "RED_A_3") (pintype "passive"))
      (node (ref "0505") (pin "3") (pinfunction "RED_A_3") (pintype "passive"))
      (node (ref "0506") (pin "3") (pinfunction "RED_A_3") (pintype "passive"))
      (node (ref "0507") (pin "3") (pinfunction "RED_A_3") (pintype "passive"))
      (node (ref "0508") (pin "3") (pinfunction "RED_A_3") (pintype "passive"))
      (node (ref "0509") (pin "3") (pinfunction "RED_A_3") (pintype "passive"))
      (node (ref "P1") (pin "33") (pinfunction "33_33") (pintype "passive"))
    )
    (net (code "19") (name "/A06B") (class "Default")
      (node (ref "0600") (pin "1") (pinfunction "BULE_A_1") (pintype "passive"))
      (node (ref "0601") (pin "1") (pinfunction "BULE_A_1") (pintype "passive"))
      (node (ref "0602") (pin "1") (pinfunction "BULE_A_1") (pintype "passive"))
      (node (ref "0603") (pin "1") (pinfunction "BULE_A_1") (pintype "passive"))
      (node (ref "0604") (pin "1") (pinfunction "BULE_A_1") (pintype "passive"))
      (node (ref "0605") (pin "1") (pinfunction "BULE_A_1") (pintype "passive"))
      (node (ref "0606") (pin "1") (pinfunction "BULE_A_1") (pintype "passive"))
      (node (ref "0607") (pin "1") (pinfunction "BULE_A_1") (pintype "passive"))
      (node (ref "0608") (pin "1") (pinfunction "BULE_A_1") (pintype "passive"))
      (node (ref "0609") (pin "1") (pinfunction "BULE_A_1") (pintype "passive"))
      (node (ref "P1") (pin "37") (pinfunction "37_37") (pintype "passive"))
    )
    (net (code "20") (name "/A06G") (class "Default")
      (node (ref "0600") (pin "5") (pinfunction "GREEN_A_5") (pintype "passive"))
      (node (ref "0601") (pin "5") (pinfunction "GREEN_A_5") (pintype "passive"))
      (node (ref "0602") (pin "5") (pinfunction "GREEN_A_5") (pintype "passive"))
      (node (ref "0603") (pin "5") (pinfunction "GREEN_A_5") (pintype "passive"))
      (node (ref "0604") (pin "5") (pinfunction "GREEN_A_5") (pintype "passive"))
      (node (ref "0605") (pin "5") (pinfunction "GREEN_A_5") (pintype "passive"))
      (node (ref "0606") (pin "5") (pinfunction "GREEN_A_5") (pintype "passive"))
      (node (ref "0607") (pin "5") (pinfunction "GREEN_A_5") (pintype "passive"))
      (node (ref "0608") (pin "5") (pinfunction "GREEN_A_5") (pintype "passive"))
      (node (ref "0609") (pin "5") (pinfunction "GREEN_A_5") (pintype "passive"))
      (node (ref "P1") (pin "41") (pinfunction "41_41") (pintype "passive"))
    )
    (net (code "21") (name "/A06R") (class "Default")
      (node (ref "0600") (pin "3") (pinfunction "RED_A_3") (pintype "passive"))
      (node (ref "0601") (pin "3") (pinfunction "RED_A_3") (pintype "passive"))
      (node (ref "0602") (pin "3") (pinfunction "RED_A_3") (pintype "passive"))
      (node (ref "0603") (pin "3") (pinfunction "RED_A_3") (pintype "passive"))
      (node (ref "0604") (pin "3") (pinfunction "RED_A_3") (pintype "passive"))
      (node (ref "0605") (pin "3") (pinfunction "RED_A_3") (pintype "passive"))
      (node (ref "0606") (pin "3") (pinfunction "RED_A_3") (pintype "passive"))
      (node (ref "0607") (pin "3") (pinfunction "RED_A_3") (pintype "passive"))
      (node (ref "0608") (pin "3") (pinfunction "RED_A_3") (pintype "passive"))
      (node (ref "0609") (pin "3") (pinfunction "RED_A_3") (pintype "passive"))
      (node (ref "P1") (pin "39") (pinfunction "39_39") (pintype "passive"))
    )
    (net (code "22") (name "/A07B") (class "Default")
      (node (ref "0700") (pin "1") (pinfunction "BULE_A_1") (pintype "passive"))
      (node (ref "0701") (pin "1") (pinfunction "BULE_A_1") (pintype "passive"))
      (node (ref "0702") (pin "1") (pinfunction "BULE_A_1") (pintype "passive"))
      (node (ref "0703") (pin "1") (pinfunction "BULE_A_1") (pintype "passive"))
      (node (ref "0704") (pin "1") (pinfunction "BULE_A_1") (pintype "passive"))
      (node (ref "0705") (pin "1") (pinfunction "BULE_A_1") (pintype "passive"))
      (node (ref "0706") (pin "1") (pinfunction "BULE_A_1") (pintype "passive"))
      (node (ref "0707") (pin "1") (pinfunction "BULE_A_1") (pintype "passive"))
      (node (ref "0708") (pin "1") (pinfunction "BULE_A_1") (pintype "passive"))
      (node (ref "0709") (pin "1") (pinfunction "BULE_A_1") (pintype "passive"))
      (node (ref "P1") (pin "43") (pinfunction "43_43") (pintype "passive"))
    )
    (net (code "23") (name "/A07G") (class "Default")
      (node (ref "0700") (pin "5") (pinfunction "GREEN_A_5") (pintype "passive"))
      (node (ref "0701") (pin "5") (pinfunction "GREEN_A_5") (pintype "passive"))
      (node (ref "0702") (pin "5") (pinfunction "GREEN_A_5") (pintype "passive"))
      (node (ref "0703") (pin "5") (pinfunction "GREEN_A_5") (pintype "passive"))
      (node (ref "0704") (pin "5") (pinfunction "GREEN_A_5") (pintype "passive"))
      (node (ref "0705") (pin "5") (pinfunction "GREEN_A_5") (pintype "passive"))
      (node (ref "0706") (pin "5") (pinfunction "GREEN_A_5") (pintype "passive"))
      (node (ref "0707") (pin "5") (pinfunction "GREEN_A_5") (pintype "passive"))
      (node (ref "0708") (pin "5") (pinfunction "GREEN_A_5") (pintype "passive"))
      (node (ref "0709") (pin "5") (pinfunction "GREEN_A_5") (pintype "passive"))
      (node (ref "P1") (pin "47") (pinfunction "47_47") (pintype "passive"))
    )
    (net (code "24") (name "/A07R") (class "Default")
      (node (ref "0700") (pin "3") (pinfunction "RED_A_3") (pintype "passive"))
      (node (ref "0701") (pin "3") (pinfunction "RED_A_3") (pintype "passive"))
      (node (ref "0702") (pin "3") (pinfunction "RED_A_3") (pintype "passive"))
      (node (ref "0703") (pin "3") (pinfunction "RED_A_3") (pintype "passive"))
      (node (ref "0704") (pin "3") (pinfunction "RED_A_3") (pintype "passive"))
      (node (ref "0705") (pin "3") (pinfunction "RED_A_3") (pintype "passive"))
      (node (ref "0706") (pin "3") (pinfunction "RED_A_3") (pintype "passive"))
      (node (ref "0707") (pin "3") (pinfunction "RED_A_3") (pintype "passive"))
      (node (ref "0708") (pin "3") (pinfunction "RED_A_3") (pintype "passive"))
      (node (ref "0709") (pin "3") (pinfunction "RED_A_3") (pintype "passive"))
      (node (ref "P1") (pin "45") (pinfunction "45_45") (pintype "passive"))
    )
    (net (code "25") (name "/A08B") (class "Default")
      (node (ref "0800") (pin "1") (pinfunction "BULE_A_1") (pintype "passive"))
      (node (ref "0801") (pin "1") (pinfunction "BULE_A_1") (pintype "passive"))
      (node (ref "0802") (pin "1") (pinfunction "BULE_A_1") (pintype "passive"))
      (node (ref "0803") (pin "1") (pinfunction "BULE_A_1") (pintype "passive"))
      (node (ref "0804") (pin "1") (pinfunction "BULE_A_1") (pintype "passive"))
      (node (ref "0805") (pin "1") (pinfunction "BULE_A_1") (pintype "passive"))
      (node (ref "0806") (pin "1") (pinfunction "BULE_A_1") (pintype "passive"))
      (node (ref "0807") (pin "1") (pinfunction "BULE_A_1") (pintype "passive"))
      (node (ref "0808") (pin "1") (pinfunction "BULE_A_1") (pintype "passive"))
      (node (ref "0809") (pin "1") (pinfunction "BULE_A_1") (pintype "passive"))
      (node (ref "P1") (pin "49") (pinfunction "49_49") (pintype "passive"))
    )
    (net (code "26") (name "/A08G") (class "Default")
      (node (ref "0800") (pin "5") (pinfunction "GREEN_A_5") (pintype "passive"))
      (node (ref "0801") (pin "5") (pinfunction "GREEN_A_5") (pintype "passive"))
      (node (ref "0802") (pin "5") (pinfunction "GREEN_A_5") (pintype "passive"))
      (node (ref "0803") (pin "5") (pinfunction "GREEN_A_5") (pintype "passive"))
      (node (ref "0804") (pin "5") (pinfunction "GREEN_A_5") (pintype "passive"))
      (node (ref "0805") (pin "5") (pinfunction "GREEN_A_5") (pintype "passive"))
      (node (ref "0806") (pin "5") (pinfunction "GREEN_A_5") (pintype "passive"))
      (node (ref "0807") (pin "5") (pinfunction "GREEN_A_5") (pintype "passive"))
      (node (ref "0808") (pin "5") (pinfunction "GREEN_A_5") (pintype "passive"))
      (node (ref "0809") (pin "5") (pinfunction "GREEN_A_5") (pintype "passive"))
      (node (ref "P1") (pin "53") (pinfunction "53_53") (pintype "passive"))
    )
    (net (code "27") (name "/A08R") (class "Default")
      (node (ref "0800") (pin "3") (pinfunction "RED_A_3") (pintype "passive"))
      (node (ref "0801") (pin "3") (pinfunction "RED_A_3") (pintype "passive"))
      (node (ref "0802") (pin "3") (pinfunction "RED_A_3") (pintype "passive"))
      (node (ref "0803") (pin "3") (pinfunction "RED_A_3") (pintype "passive"))
      (node (ref "0804") (pin "3") (pinfunction "RED_A_3") (pintype "passive"))
      (node (ref "0805") (pin "3") (pinfunction "RED_A_3") (pintype "passive"))
      (node (ref "0806") (pin "3") (pinfunction "RED_A_3") (pintype "passive"))
      (node (ref "0807") (pin "3") (pinfunction "RED_A_3") (pintype "passive"))
      (node (ref "0808") (pin "3") (pinfunction "RED_A_3") (pintype "passive"))
      (node (ref "0809") (pin "3") (pinfunction "RED_A_3") (pintype "passive"))
      (node (ref "P1") (pin "51") (pinfunction "51_51") (pintype "passive"))
    )
    (net (code "28") (name "/A09B") (class "Default")
      (node (ref "0900") (pin "1") (pinfunction "BULE_A_1") (pintype "passive"))
      (node (ref "0901") (pin "1") (pinfunction "BULE_A_1") (pintype "passive"))
      (node (ref "0902") (pin "1") (pinfunction "BULE_A_1") (pintype "passive"))
      (node (ref "0903") (pin "1") (pinfunction "BULE_A_1") (pintype "passive"))
      (node (ref "0904") (pin "1") (pinfunction "BULE_A_1") (pintype "passive"))
      (node (ref "0905") (pin "1") (pinfunction "BULE_A_1") (pintype "passive"))
      (node (ref "0906") (pin "1") (pinfunction "BULE_A_1") (pintype "passive"))
      (node (ref "0907") (pin "1") (pinfunction "BULE_A_1") (pintype "passive"))
      (node (ref "0908") (pin "1") (pinfunction "BULE_A_1") (pintype "passive"))
      (node (ref "0909") (pin "1") (pinfunction "BULE_A_1") (pintype "passive"))
      (node (ref "P1") (pin "55") (pinfunction "55_55") (pintype "passive"))
    )
    (net (code "29") (name "/A09G") (class "Default")
      (node (ref "0900") (pin "5") (pinfunction "GREEN_A_5") (pintype "passive"))
      (node (ref "0901") (pin "5") (pinfunction "GREEN_A_5") (pintype "passive"))
      (node (ref "0902") (pin "5") (pinfunction "GREEN_A_5") (pintype "passive"))
      (node (ref "0903") (pin "5") (pinfunction "GREEN_A_5") (pintype "passive"))
      (node (ref "0904") (pin "5") (pinfunction "GREEN_A_5") (pintype "passive"))
      (node (ref "0905") (pin "5") (pinfunction "GREEN_A_5") (pintype "passive"))
      (node (ref "0906") (pin "5") (pinfunction "GREEN_A_5") (pintype "passive"))
      (node (ref "0907") (pin "5") (pinfunction "GREEN_A_5") (pintype "passive"))
      (node (ref "0908") (pin "5") (pinfunction "GREEN_A_5") (pintype "passive"))
      (node (ref "0909") (pin "5") (pinfunction "GREEN_A_5") (pintype "passive"))
      (node (ref "P1") (pin "59") (pinfunction "59_59") (pintype "passive"))
    )
    (net (code "30") (name "/A09R") (class "Default")
      (node (ref "0900") (pin "3") (pinfunction "RED_A_3") (pintype "passive"))
      (node (ref "0901") (pin "3") (pinfunction "RED_A_3") (pintype "passive"))
      (node (ref "0902") (pin "3") (pinfunction "RED_A_3") (pintype "passive"))
      (node (ref "0903") (pin "3") (pinfunction "RED_A_3") (pintype "passive"))
      (node (ref "0904") (pin "3") (pinfunction "RED_A_3") (pintype "passive"))
      (node (ref "0905") (pin "3") (pinfunction "RED_A_3") (pintype "passive"))
      (node (ref "0906") (pin "3") (pinfunction "RED_A_3") (pintype "passive"))
      (node (ref "0907") (pin "3") (pinfunction "RED_A_3") (pintype "passive"))
      (node (ref "0908") (pin "3") (pinfunction "RED_A_3") (pintype "passive"))
      (node (ref "0909") (pin "3") (pinfunction "RED_A_3") (pintype "passive"))
      (node (ref "P1") (pin "57") (pinfunction "57_57") (pintype "passive"))
    )
    (net (code "31") (name "/C00") (class "Default")
      (node (ref "0000") (pin "2") (pinfunction "BULE_K_2") (pintype "passive"))
      (node (ref "0000") (pin "4") (pinfunction "RED_K_4") (pintype "passive"))
      (node (ref "0000") (pin "6") (pinfunction "GREEN_K_6") (pintype "passive"))
      (node (ref "0100") (pin "2") (pinfunction "BULE_K_2") (pintype "passive"))
      (node (ref "0100") (pin "4") (pinfunction "RED_K_4") (pintype "passive"))
      (node (ref "0100") (pin "6") (pinfunction "GREEN_K_6") (pintype "passive"))
      (node (ref "0200") (pin "2") (pinfunction "BULE_K_2") (pintype "passive"))
      (node (ref "0200") (pin "4") (pinfunction "RED_K_4") (pintype "passive"))
      (node (ref "0200") (pin "6") (pinfunction "GREEN_K_6") (pintype "passive"))
      (node (ref "0300") (pin "2") (pinfunction "BULE_K_2") (pintype "passive"))
      (node (ref "0300") (pin "4") (pinfunction "RED_K_4") (pintype "passive"))
      (node (ref "0300") (pin "6") (pinfunction "GREEN_K_6") (pintype "passive"))
      (node (ref "0400") (pin "2") (pinfunction "BULE_K_2") (pintype "passive"))
      (node (ref "0400") (pin "4") (pinfunction "RED_K_4") (pintype "passive"))
      (node (ref "0400") (pin "6") (pinfunction "GREEN_K_6") (pintype "passive"))
      (node (ref "0500") (pin "2") (pinfunction "BULE_K_2") (pintype "passive"))
      (node (ref "0500") (pin "4") (pinfunction "RED_K_4") (pintype "passive"))
      (node (ref "0500") (pin "6") (pinfunction "GREEN_K_6") (pintype "passive"))
      (node (ref "0600") (pin "2") (pinfunction "BULE_K_2") (pintype "passive"))
      (node (ref "0600") (pin "4") (pinfunction "RED_K_4") (pintype "passive"))
      (node (ref "0600") (pin "6") (pinfunction "GREEN_K_6") (pintype "passive"))
      (node (ref "0700") (pin "2") (pinfunction "BULE_K_2") (pintype "passive"))
      (node (ref "0700") (pin "4") (pinfunction "RED_K_4") (pintype "passive"))
      (node (ref "0700") (pin "6") (pinfunction "GREEN_K_6") (pintype "passive"))
      (node (ref "0800") (pin "2") (pinfunction "BULE_K_2") (pintype "passive"))
      (node (ref "0800") (pin "4") (pinfunction "RED_K_4") (pintype "passive"))
      (node (ref "0800") (pin "6") (pinfunction "GREEN_K_6") (pintype "passive"))
      (node (ref "0900") (pin "2") (pinfunction "BULE_K_2") (pintype "passive"))
      (node (ref "0900") (pin "4") (pinfunction "RED_K_4") (pintype "passive"))
      (node (ref "0900") (pin "6") (pinfunction "GREEN_K_6") (pintype "passive"))
      (node (ref "P1") (pin "2") (pinfunction "2_2") (pintype "passive"))
      (node (ref "P1") (pin "4") (pinfunction "4_4") (pintype "passive"))
      (node (ref "P1") (pin "6") (pinfunction "6_6") (pintype "passive"))
    )
    (net (code "32") (name "/C01") (class "Default")
      (node (ref "0001") (pin "2") (pinfunction "BULE_K_2") (pintype "passive"))
      (node (ref "0001") (pin "4") (pinfunction "RED_K_4") (pintype "passive"))
      (node (ref "0001") (pin "6") (pinfunction "GREEN_K_6") (pintype "passive"))
      (node (ref "0101") (pin "2") (pinfunction "BULE_K_2") (pintype "passive"))
      (node (ref "0101") (pin "4") (pinfunction "RED_K_4") (pintype "passive"))
      (node (ref "0101") (pin "6") (pinfunction "GREEN_K_6") (pintype "passive"))
      (node (ref "0201") (pin "2") (pinfunction "BULE_K_2") (pintype "passive"))
      (node (ref "0201") (pin "4") (pinfunction "RED_K_4") (pintype "passive"))
      (node (ref "0201") (pin "6") (pinfunction "GREEN_K_6") (pintype "passive"))
      (node (ref "0301") (pin "2") (pinfunction "BULE_K_2") (pintype "passive"))
      (node (ref "0301") (pin "4") (pinfunction "RED_K_4") (pintype "passive"))
      (node (ref "0301") (pin "6") (pinfunction "GREEN_K_6") (pintype "passive"))
      (node (ref "0401") (pin "2") (pinfunction "BULE_K_2") (pintype "passive"))
      (node (ref "0401") (pin "4") (pinfunction "RED_K_4") (pintype "passive"))
      (node (ref "0401") (pin "6") (pinfunction "GREEN_K_6") (pintype "passive"))
      (node (ref "0501") (pin "2") (pinfunction "BULE_K_2") (pintype "passive"))
      (node (ref "0501") (pin "4") (pinfunction "RED_K_4") (pintype "passive"))
      (node (ref "0501") (pin "6") (pinfunction "GREEN_K_6") (pintype "passive"))
      (node (ref "0601") (pin "2") (pinfunction "BULE_K_2") (pintype "passive"))
      (node (ref "0601") (pin "4") (pinfunction "RED_K_4") (pintype "passive"))
      (node (ref "0601") (pin "6") (pinfunction "GREEN_K_6") (pintype "passive"))
      (node (ref "0701") (pin "2") (pinfunction "BULE_K_2") (pintype "passive"))
      (node (ref "0701") (pin "4") (pinfunction "RED_K_4") (pintype "passive"))
      (node (ref "0701") (pin "6") (pinfunction "GREEN_K_6") (pintype "passive"))
      (node (ref "0801") (pin "2") (pinfunction "BULE_K_2") (pintype "passive"))
      (node (ref "0801") (pin "4") (pinfunction "RED_K_4") (pintype "passive"))
      (node (ref "0801") (pin "6") (pinfunction "GREEN_K_6") (pintype "passive"))
      (node (ref "0901") (pin "2") (pinfunction "BULE_K_2") (pintype "passive"))
      (node (ref "0901") (pin "4") (pinfunction "RED_K_4") (pintype "passive"))
      (node (ref "0901") (pin "6") (pinfunction "GREEN_K_6") (pintype "passive"))
      (node (ref "P1") (pin "10") (pinfunction "10_10") (pintype "passive"))
      (node (ref "P1") (pin "12") (pinfunction "12_12") (pintype "passive"))
      (node (ref "P1") (pin "8") (pinfunction "8_8") (pintype "passive"))
    )
    (net (code "33") (name "/C02") (class "Default")
      (node (ref "0002") (pin "2") (pinfunction "BULE_K_2") (pintype "passive"))
      (node (ref "0002") (pin "4") (pinfunction "RED_K_4") (pintype "passive"))
      (node (ref "0002") (pin "6") (pinfunction "GREEN_K_6") (pintype "passive"))
      (node (ref "0102") (pin "2") (pinfunction "BULE_K_2") (pintype "passive"))
      (node (ref "0102") (pin "4") (pinfunction "RED_K_4") (pintype "passive"))
      (node (ref "0102") (pin "6") (pinfunction "GREEN_K_6") (pintype "passive"))
      (node (ref "0202") (pin "2") (pinfunction "BULE_K_2") (pintype "passive"))
      (node (ref "0202") (pin "4") (pinfunction "RED_K_4") (pintype "passive"))
      (node (ref "0202") (pin "6") (pinfunction "GREEN_K_6") (pintype "passive"))
      (node (ref "0302") (pin "2") (pinfunction "BULE_K_2") (pintype "passive"))
      (node (ref "0302") (pin "4") (pinfunction "RED_K_4") (pintype "passive"))
      (node (ref "0302") (pin "6") (pinfunction "GREEN_K_6") (pintype "passive"))
      (node (ref "0402") (pin "2") (pinfunction "BULE_K_2") (pintype "passive"))
      (node (ref "0402") (pin "4") (pinfunction "RED_K_4") (pintype "passive"))
      (node (ref "0402") (pin "6") (pinfunction "GREEN_K_6") (pintype "passive"))
      (node (ref "0502") (pin "2") (pinfunction "BULE_K_2") (pintype "passive"))
      (node (ref "0502") (pin "4") (pinfunction "RED_K_4") (pintype "passive"))
      (node (ref "0502") (pin "6") (pinfunction "GREEN_K_6") (pintype "passive"))
      (node (ref "0602") (pin "2") (pinfunction "BULE_K_2") (pintype "passive"))
      (node (ref "0602") (pin "4") (pinfunction "RED_K_4") (pintype "passive"))
      (node (ref "0602") (pin "6") (pinfunction "GREEN_K_6") (pintype "passive"))
      (node (ref "0702") (pin "2") (pinfunction "BULE_K_2") (pintype "passive"))
      (node (ref "0702") (pin "4") (pinfunction "RED_K_4") (pintype "passive"))
      (node (ref "0702") (pin "6") (pinfunction "GREEN_K_6") (pintype "passive"))
      (node (ref "0802") (pin "2") (pinfunction "BULE_K_2") (pintype "passive"))
      (node (ref "0802") (pin "4") (pinfunction "RED_K_4") (pintype "passive"))
      (node (ref "0802") (pin "6") (pinfunction "GREEN_K_6") (pintype "passive"))
      (node (ref "0902") (pin "2") (pinfunction "BULE_K_2") (pintype "passive"))
      (node (ref "0902") (pin "4") (pinfunction "RED_K_4") (pintype "passive"))
      (node (ref "0902") (pin "6") (pinfunction "GREEN_K_6") (pintype "passive"))
      (node (ref "P1") (pin "14") (pinfunction "14_14") (pintype "passive"))
      (node (ref "P1") (pin "16") (pinfunction "16_16") (pintype "passive"))
      (node (ref "P1") (pin "18") (pinfunction "18_18") (pintype "passive"))
    )
    (net (code "34") (name "/C03") (class "Default")
      (node (ref "0003") (pin "2") (pinfunction "BULE_K_2") (pintype "passive"))
      (node (ref "0003") (pin "4") (pinfunction "RED_K_4") (pintype "passive"))
      (node (ref "0003") (pin "6") (pinfunction "GREEN_K_6") (pintype "passive"))
      (node (ref "0103") (pin "2") (pinfunction "BULE_K_2") (pintype "passive"))
      (node (ref "0103") (pin "4") (pinfunction "RED_K_4") (pintype "passive"))
      (node (ref "0103") (pin "6") (pinfunction "GREEN_K_6") (pintype "passive"))
      (node (ref "0203") (pin "2") (pinfunction "BULE_K_2") (pintype "passive"))
      (node (ref "0203") (pin "4") (pinfunction "RED_K_4") (pintype "passive"))
      (node (ref "0203") (pin "6") (pinfunction "GREEN_K_6") (pintype "passive"))
      (node (ref "0303") (pin "2") (pinfunction "BULE_K_2") (pintype "passive"))
      (node (ref "0303") (pin "4") (pinfunction "RED_K_4") (pintype "passive"))
      (node (ref "0303") (pin "6") (pinfunction "GREEN_K_6") (pintype "passive"))
      (node (ref "0403") (pin "2") (pinfunction "BULE_K_2") (pintype "passive"))
      (node (ref "0403") (pin "4") (pinfunction "RED_K_4") (pintype "passive"))
      (node (ref "0403") (pin "6") (pinfunction "GREEN_K_6") (pintype "passive"))
      (node (ref "0503") (pin "2") (pinfunction "BULE_K_2") (pintype "passive"))
      (node (ref "0503") (pin "4") (pinfunction "RED_K_4") (pintype "passive"))
      (node (ref "0503") (pin "6") (pinfunction "GREEN_K_6") (pintype "passive"))
      (node (ref "0603") (pin "2") (pinfunction "BULE_K_2") (pintype "passive"))
      (node (ref "0603") (pin "4") (pinfunction "RED_K_4") (pintype "passive"))
      (node (ref "0603") (pin "6") (pinfunction "GREEN_K_6") (pintype "passive"))
      (node (ref "0703") (pin "2") (pinfunction "BULE_K_2") (pintype "passive"))
      (node (ref "0703") (pin "4") (pinfunction "RED_K_4") (pintype "passive"))
      (node (ref "0703") (pin "6") (pinfunction "GREEN_K_6") (pintype "passive"))
      (node (ref "0803") (pin "2") (pinfunction "BULE_K_2") (pintype "passive"))
      (node (ref "0803") (pin "4") (pinfunction "RED_K_4") (pintype "passive"))
      (node (ref "0803") (pin "6") (pinfunction "GREEN_K_6") (pintype "passive"))
      (node (ref "0903") (pin "2") (pinfunction "BULE_K_2") (pintype "passive"))
      (node (ref "0903") (pin "4") (pinfunction "RED_K_4") (pintype "passive"))
      (node (ref "0903") (pin "6") (pinfunction "GREEN_K_6") (pintype "passive"))
      (node (ref "P1") (pin "20") (pinfunction "20_20") (pintype "passive"))
      (node (ref "P1") (pin "22") (pinfunction "22_22") (pintype "passive"))
      (node (ref "P1") (pin "24") (pinfunction "24_24") (pintype "passive"))
    )
    (net (code "35") (name "/C04") (class "Default")
      (node (ref "0004") (pin "2") (pinfunction "BULE_K_2") (pintype "passive"))
      (node (ref "0004") (pin "4") (pinfunction "RED_K_4") (pintype "passive"))
      (node (ref "0004") (pin "6") (pinfunction "GREEN_K_6") (pintype "passive"))
      (node (ref "0104") (pin "2") (pinfunction "BULE_K_2") (pintype "passive"))
      (node (ref "0104") (pin "4") (pinfunction "RED_K_4") (pintype "passive"))
      (node (ref "0104") (pin "6") (pinfunction "GREEN_K_6") (pintype "passive"))
      (node (ref "0204") (pin "2") (pinfunction "BULE_K_2") (pintype "passive"))
      (node (ref "0204") (pin "4") (pinfunction "RED_K_4") (pintype "passive"))
      (node (ref "0204") (pin "6") (pinfunction "GREEN_K_6") (pintype "passive"))
      (node (ref "0304") (pin "2") (pinfunction "BULE_K_2") (pintype "passive"))
      (node (ref "0304") (pin "4") (pinfunction "RED_K_4") (pintype "passive"))
      (node (ref "0304") (pin "6") (pinfunction "GREEN_K_6") (pintype "passive"))
      (node (ref "0404") (pin "2") (pinfunction "BULE_K_2") (pintype "passive"))
      (node (ref "0404") (pin "4") (pinfunction "RED_K_4") (pintype "passive"))
      (node (ref "0404") (pin "6") (pinfunction "GREEN_K_6") (pintype "passive"))
      (node (ref "0504") (pin "2") (pinfunction "BULE_K_2") (pintype "passive"))
      (node (ref "0504") (pin "4") (pinfunction "RED_K_4") (pintype "passive"))
      (node (ref "0504") (pin "6") (pinfunction "GREEN_K_6") (pintype "passive"))
      (node (ref "0604") (pin "2") (pinfunction "BULE_K_2") (pintype "passive"))
      (node (ref "0604") (pin "4") (pinfunction "RED_K_4") (pintype "passive"))
      (node (ref "0604") (pin "6") (pinfunction "GREEN_K_6") (pintype "passive"))
      (node (ref "0704") (pin "2") (pinfunction "BULE_K_2") (pintype "passive"))
      (node (ref "0704") (pin "4") (pinfunction "RED_K_4") (pintype "passive"))
      (node (ref "0704") (pin "6") (pinfunction "GREEN_K_6") (pintype "passive"))
      (node (ref "0804") (pin "2") (pinfunction "BULE_K_2") (pintype "passive"))
      (node (ref "0804") (pin "4") (pinfunction "RED_K_4") (pintype "passive"))
      (node (ref "0804") (pin "6") (pinfunction "GREEN_K_6") (pintype "passive"))
      (node (ref "0904") (pin "2") (pinfunction "BULE_K_2") (pintype "passive"))
      (node (ref "0904") (pin "4") (pinfunction "RED_K_4") (pintype "passive"))
      (node (ref "0904") (pin "6") (pinfunction "GREEN_K_6") (pintype "passive"))
      (node (ref "P1") (pin "26") (pinfunction "26_26") (pintype "passive"))
      (node (ref "P1") (pin "28") (pinfunction "28_28") (pintype "passive"))
      (node (ref "P1") (pin "30") (pinfunction "30_30") (pintype "passive"))
    )
    (net (code "36") (name "/C05") (class "Default")
      (node (ref "0005") (pin "2") (pinfunction "BULE_K_2") (pintype "passive"))
      (node (ref "0005") (pin "4") (pinfunction "RED_K_4") (pintype "passive"))
      (node (ref "0005") (pin "6") (pinfunction "GREEN_K_6") (pintype "passive"))
      (node (ref "0105") (pin "2") (pinfunction "BULE_K_2") (pintype "passive"))
      (node (ref "0105") (pin "4") (pinfunction "RED_K_4") (pintype "passive"))
      (node (ref "0105") (pin "6") (pinfunction "GREEN_K_6") (pintype "passive"))
      (node (ref "0205") (pin "2") (pinfunction "BULE_K_2") (pintype "passive"))
      (node (ref "0205") (pin "4") (pinfunction "RED_K_4") (pintype "passive"))
      (node (ref "0205") (pin "6") (pinfunction "GREEN_K_6") (pintype "passive"))
      (node (ref "0305") (pin "2") (pinfunction "BULE_K_2") (pintype "passive"))
      (node (ref "0305") (pin "4") (pinfunction "RED_K_4") (pintype "passive"))
      (node (ref "0305") (pin "6") (pinfunction "GREEN_K_6") (pintype "passive"))
      (node (ref "0405") (pin "2") (pinfunction "BULE_K_2") (pintype "passive"))
      (node (ref "0405") (pin "4") (pinfunction "RED_K_4") (pintype "passive"))
      (node (ref "0405") (pin "6") (pinfunction "GREEN_K_6") (pintype "passive"))
      (node (ref "0505") (pin "2") (pinfunction "BULE_K_2") (pintype "passive"))
      (node (ref "0505") (pin "4") (pinfunction "RED_K_4") (pintype "passive"))
      (node (ref "0505") (pin "6") (pinfunction "GREEN_K_6") (pintype "passive"))
      (node (ref "0605") (pin "2") (pinfunction "BULE_K_2") (pintype "passive"))
      (node (ref "0605") (pin "4") (pinfunction "RED_K_4") (pintype "passive"))
      (node (ref "0605") (pin "6") (pinfunction "GREEN_K_6") (pintype "passive"))
      (node (ref "0705") (pin "2") (pinfunction "BULE_K_2") (pintype "passive"))
      (node (ref "0705") (pin "4") (pinfunction "RED_K_4") (pintype "passive"))
      (node (ref "0705") (pin "6") (pinfunction "GREEN_K_6") (pintype "passive"))
      (node (ref "0805") (pin "2") (pinfunction "BULE_K_2") (pintype "passive"))
      (node (ref "0805") (pin "4") (pinfunction "RED_K_4") (pintype "passive"))
      (node (ref "0805") (pin "6") (pinfunction "GREEN_K_6") (pintype "passive"))
      (node (ref "0905") (pin "2") (pinfunction "BULE_K_2") (pintype "passive"))
      (node (ref "0905") (pin "4") (pinfunction "RED_K_4") (pintype "passive"))
      (node (ref "0905") (pin "6") (pinfunction "GREEN_K_6") (pintype "passive"))
      (node (ref "P1") (pin "32") (pinfunction "32_32") (pintype "passive"))
      (node (ref "P1") (pin "34") (pinfunction "34_34") (pintype "passive"))
      (node (ref "P1") (pin "36") (pinfunction "36_36") (pintype "passive"))
    )
    (net (code "37") (name "/C06") (class "Default")
      (node (ref "0006") (pin "2") (pinfunction "BULE_K_2") (pintype "passive"))
      (node (ref "0006") (pin "4") (pinfunction "RED_K_4") (pintype "passive"))
      (node (ref "0006") (pin "6") (pinfunction "GREEN_K_6") (pintype "passive"))
      (node (ref "0106") (pin "2") (pinfunction "BULE_K_2") (pintype "passive"))
      (node (ref "0106") (pin "4") (pinfunction "RED_K_4") (pintype "passive"))
      (node (ref "0106") (pin "6") (pinfunction "GREEN_K_6") (pintype "passive"))
      (node (ref "0206") (pin "2") (pinfunction "BULE_K_2") (pintype "passive"))
      (node (ref "0206") (pin "4") (pinfunction "RED_K_4") (pintype "passive"))
      (node (ref "0206") (pin "6") (pinfunction "GREEN_K_6") (pintype "passive"))
      (node (ref "0306") (pin "2") (pinfunction "BULE_K_2") (pintype "passive"))
      (node (ref "0306") (pin "4") (pinfunction "RED_K_4") (pintype "passive"))
      (node (ref "0306") (pin "6") (pinfunction "GREEN_K_6") (pintype "passive"))
      (node (ref "0406") (pin "2") (pinfunction "BULE_K_2") (pintype "passive"))
      (node (ref "0406") (pin "4") (pinfunction "RED_K_4") (pintype "passive"))
      (node (ref "0406") (pin "6") (pinfunction "GREEN_K_6") (pintype "passive"))
      (node (ref "0506") (pin "2") (pinfunction "BULE_K_2") (pintype "passive"))
      (node (ref "0506") (pin "4") (pinfunction "RED_K_4") (pintype "passive"))
      (node (ref "0506") (pin "6") (pinfunction "GREEN_K_6") (pintype "passive"))
      (node (ref "0606") (pin "2") (pinfunction "BULE_K_2") (pintype "passive"))
      (node (ref "0606") (pin "4") (pinfunction "RED_K_4") (pintype "passive"))
      (node (ref "0606") (pin "6") (pinfunction "GREEN_K_6") (pintype "passive"))
      (node (ref "0706") (pin "2") (pinfunction "BULE_K_2") (pintype "passive"))
      (node (ref "0706") (pin "4") (pinfunction "RED_K_4") (pintype "passive"))
      (node (ref "0706") (pin "6") (pinfunction "GREEN_K_6") (pintype "passive"))
      (node (ref "0806") (pin "2") (pinfunction "BULE_K_2") (pintype "passive"))
      (node (ref "0806") (pin "4") (pinfunction "RED_K_4") (pintype "passive"))
      (node (ref "0806") (pin "6") (pinfunction "GREEN_K_6") (pintype "passive"))
      (node (ref "0906") (pin "2") (pinfunction "BULE_K_2") (pintype "passive"))
      (node (ref "0906") (pin "4") (pinfunction "RED_K_4") (pintype "passive"))
      (node (ref "0906") (pin "6") (pinfunction "GREEN_K_6") (pintype "passive"))
      (node (ref "P1") (pin "38") (pinfunction "38_38") (pintype "passive"))
      (node (ref "P1") (pin "40") (pinfunction "40_40") (pintype "passive"))
      (node (ref "P1") (pin "42") (pinfunction "42_42") (pintype "passive"))
    )
    (net (code "38") (name "/C07") (class "Default")
      (node (ref "0007") (pin "2") (pinfunction "BULE_K_2") (pintype "passive"))
      (node (ref "0007") (pin "4") (pinfunction "RED_K_4") (pintype "passive"))
      (node (ref "0007") (pin "6") (pinfunction "GREEN_K_6") (pintype "passive"))
      (node (ref "0107") (pin "2") (pinfunction "BULE_K_2") (pintype "passive"))
      (node (ref "0107") (pin "4") (pinfunction "RED_K_4") (pintype "passive"))
      (node (ref "0107") (pin "6") (pinfunction "GREEN_K_6") (pintype "passive"))
      (node (ref "0207") (pin "2") (pinfunction "BULE_K_2") (pintype "passive"))
      (node (ref "0207") (pin "4") (pinfunction "RED_K_4") (pintype "passive"))
      (node (ref "0207") (pin "6") (pinfunction "GREEN_K_6") (pintype "passive"))
      (node (ref "0307") (pin "2") (pinfunction "BULE_K_2") (pintype "passive"))
      (node (ref "0307") (pin "4") (pinfunction "RED_K_4") (pintype "passive"))
      (node (ref "0307") (pin "6") (pinfunction "GREEN_K_6") (pintype "passive"))
      (node (ref "0407") (pin "2") (pinfunction "BULE_K_2") (pintype "passive"))
      (node (ref "0407") (pin "4") (pinfunction "RED_K_4") (pintype "passive"))
      (node (ref "0407") (pin "6") (pinfunction "GREEN_K_6") (pintype "passive"))
      (node (ref "0507") (pin "2") (pinfunction "BULE_K_2") (pintype "passive"))
      (node (ref "0507") (pin "4") (pinfunction "RED_K_4") (pintype "passive"))
      (node (ref "0507") (pin "6") (pinfunction "GREEN_K_6") (pintype "passive"))
      (node (ref "0607") (pin "2") (pinfunction "BULE_K_2") (pintype "passive"))
      (node (ref "0607") (pin "4") (pinfunction "RED_K_4") (pintype "passive"))
      (node (ref "0607") (pin "6") (pinfunction "GREEN_K_6") (pintype "passive"))
      (node (ref "0707") (pin "2") (pinfunction "BULE_K_2") (pintype "passive"))
      (node (ref "0707") (pin "4") (pinfunction "RED_K_4") (pintype "passive"))
      (node (ref "0707") (pin "6") (pinfunction "GREEN_K_6") (pintype "passive"))
      (node (ref "0807") (pin "2") (pinfunction "BULE_K_2") (pintype "passive"))
      (node (ref "0807") (pin "4") (pinfunction "RED_K_4") (pintype "passive"))
      (node (ref "0807") (pin "6") (pinfunction "GREEN_K_6") (pintype "passive"))
      (node (ref "0907") (pin "2") (pinfunction "BULE_K_2") (pintype "passive"))
      (node (ref "0907") (pin "4") (pinfunction "RED_K_4") (pintype "passive"))
      (node (ref "0907") (pin "6") (pinfunction "GREEN_K_6") (pintype "passive"))
      (node (ref "P1") (pin "44") (pinfunction "44_44") (pintype "passive"))
      (node (ref "P1") (pin "46") (pinfunction "46_46") (pintype "passive"))
      (node (ref "P1") (pin "48") (pinfunction "48_48") (pintype "passive"))
    )
    (net (code "39") (name "/C08") (class "Default")
      (node (ref "0008") (pin "2") (pinfunction "BULE_K_2") (pintype "passive"))
      (node (ref "0008") (pin "4") (pinfunction "RED_K_4") (pintype "passive"))
      (node (ref "0008") (pin "6") (pinfunction "GREEN_K_6") (pintype "passive"))
      (node (ref "0108") (pin "2") (pinfunction "BULE_K_2") (pintype "passive"))
      (node (ref "0108") (pin "4") (pinfunction "RED_K_4") (pintype "passive"))
      (node (ref "0108") (pin "6") (pinfunction "GREEN_K_6") (pintype "passive"))
      (node (ref "0208") (pin "2") (pinfunction "BULE_K_2") (pintype "passive"))
      (node (ref "0208") (pin "4") (pinfunction "RED_K_4") (pintype "passive"))
      (node (ref "0208") (pin "6") (pinfunction "GREEN_K_6") (pintype "passive"))
      (node (ref "0308") (pin "2") (pinfunction "BULE_K_2") (pintype "passive"))
      (node (ref "0308") (pin "4") (pinfunction "RED_K_4") (pintype "passive"))
      (node (ref "0308") (pin "6") (pinfunction "GREEN_K_6") (pintype "passive"))
      (node (ref "0408") (pin "2") (pinfunction "BULE_K_2") (pintype "passive"))
      (node (ref "0408") (pin "4") (pinfunction "RED_K_4") (pintype "passive"))
      (node (ref "0408") (pin "6") (pinfunction "GREEN_K_6") (pintype "passive"))
      (node (ref "0508") (pin "2") (pinfunction "BULE_K_2") (pintype "passive"))
      (node (ref "0508") (pin "4") (pinfunction "RED_K_4") (pintype "passive"))
      (node (ref "0508") (pin "6") (pinfunction "GREEN_K_6") (pintype "passive"))
      (node (ref "0608") (pin "2") (pinfunction "BULE_K_2") (pintype "passive"))
      (node (ref "0608") (pin "4") (pinfunction "RED_K_4") (pintype "passive"))
      (node (ref "0608") (pin "6") (pinfunction "GREEN_K_6") (pintype "passive"))
      (node (ref "0708") (pin "2") (pinfunction "BULE_K_2") (pintype "passive"))
      (node (ref "0708") (pin "4") (pinfunction "RED_K_4") (pintype "passive"))
      (node (ref "0708") (pin "6") (pinfunction "GREEN_K_6") (pintype "passive"))
      (node (ref "0808") (pin "2") (pinfunction "BULE_K_2") (pintype "passive"))
      (node (ref "0808") (pin "4") (pinfunction "RED_K_4") (pintype "passive"))
      (node (ref "0808") (pin "6") (pinfunction "GREEN_K_6") (pintype "passive"))
      (node (ref "0908") (pin "2") (pinfunction "BULE_K_2") (pintype "passive"))
      (node (ref "0908") (pin "4") (pinfunction "RED_K_4") (pintype "passive"))
      (node (ref "0908") (pin "6") (pinfunction "GREEN_K_6") (pintype "passive"))
      (node (ref "P1") (pin "50") (pinfunction "50_50") (pintype "passive"))
      (node (ref "P1") (pin "52") (pinfunction "52_52") (pintype "passive"))
      (node (ref "P1") (pin "54") (pinfunction "54_54") (pintype "passive"))
    )
    (net (code "40") (name "/C09") (class "Default")
      (node (ref "0009") (pin "2") (pinfunction "BULE_K_2") (pintype "passive"))
      (node (ref "0009") (pin "4") (pinfunction "RED_K_4") (pintype "passive"))
      (node (ref "0009") (pin "6") (pinfunction "GREEN_K_6") (pintype "passive"))
      (node (ref "0109") (pin "2") (pinfunction "BULE_K_2") (pintype "passive"))
      (node (ref "0109") (pin "4") (pinfunction "RED_K_4") (pintype "passive"))
      (node (ref "0109") (pin "6") (pinfunction "GREEN_K_6") (pintype "passive"))
      (node (ref "0209") (pin "2") (pinfunction "BULE_K_2") (pintype "passive"))
      (node (ref "0209") (pin "4") (pinfunction "RED_K_4") (pintype "passive"))
      (node (ref "0209") (pin "6") (pinfunction "GREEN_K_6") (pintype "passive"))
      (node (ref "0309") (pin "2") (pinfunction "BULE_K_2") (pintype "passive"))
      (node (ref "0309") (pin "4") (pinfunction "RED_K_4") (pintype "passive"))
      (node (ref "0309") (pin "6") (pinfunction "GREEN_K_6") (pintype "passive"))
      (node (ref "0409") (pin "2") (pinfunction "BULE_K_2") (pintype "passive"))
      (node (ref "0409") (pin "4") (pinfunction "RED_K_4") (pintype "passive"))
      (node (ref "0409") (pin "6") (pinfunction "GREEN_K_6") (pintype "passive"))
      (node (ref "0509") (pin "2") (pinfunction "BULE_K_2") (pintype "passive"))
      (node (ref "0509") (pin "4") (pinfunction "RED_K_4") (pintype "passive"))
      (node (ref "0509") (pin "6") (pinfunction "GREEN_K_6") (pintype "passive"))
      (node (ref "0609") (pin "2") (pinfunction "BULE_K_2") (pintype "passive"))
      (node (ref "0609") (pin "4") (pinfunction "RED_K_4") (pintype "passive"))
      (node (ref "0609") (pin "6") (pinfunction "GREEN_K_6") (pintype "passive"))
      (node (ref "0709") (pin "2") (pinfunction "BULE_K_2") (pintype "passive"))
      (node (ref "0709") (pin "4") (pinfunction "RED_K_4") (pintype "passive"))
      (node (ref "0709") (pin "6") (pinfunction "GREEN_K_6") (pintype "passive"))
      (node (ref "0809") (pin "2") (pinfunction "BULE_K_2") (pintype "passive"))
      (node (ref "0809") (pin "4") (pinfunction "RED_K_4") (pintype "passive"))
      (node (ref "0809") (pin "6") (pinfunction "GREEN_K_6") (pintype "passive"))
      (node (ref "0909") (pin "2") (pinfunction "BULE_K_2") (pintype "passive"))
      (node (ref "0909") (pin "4") (pinfunction "RED_K_4") (pintype "passive"))
      (node (ref "0909") (pin "6") (pinfunction "GREEN_K_6") (pintype "passive"))
      (node (ref "P1") (pin "56") (pinfunction "56_56") (pintype "passive"))
      (node (ref "P1") (pin "58") (pinfunction "58_58") (pintype "passive"))
      (node (ref "P1") (pin "60") (pinfunction "60_60") (pintype "passive"))
    )
  )
)
